# Decoder16_1.net
KiCad netlist of a schematic drawn in EAGLE
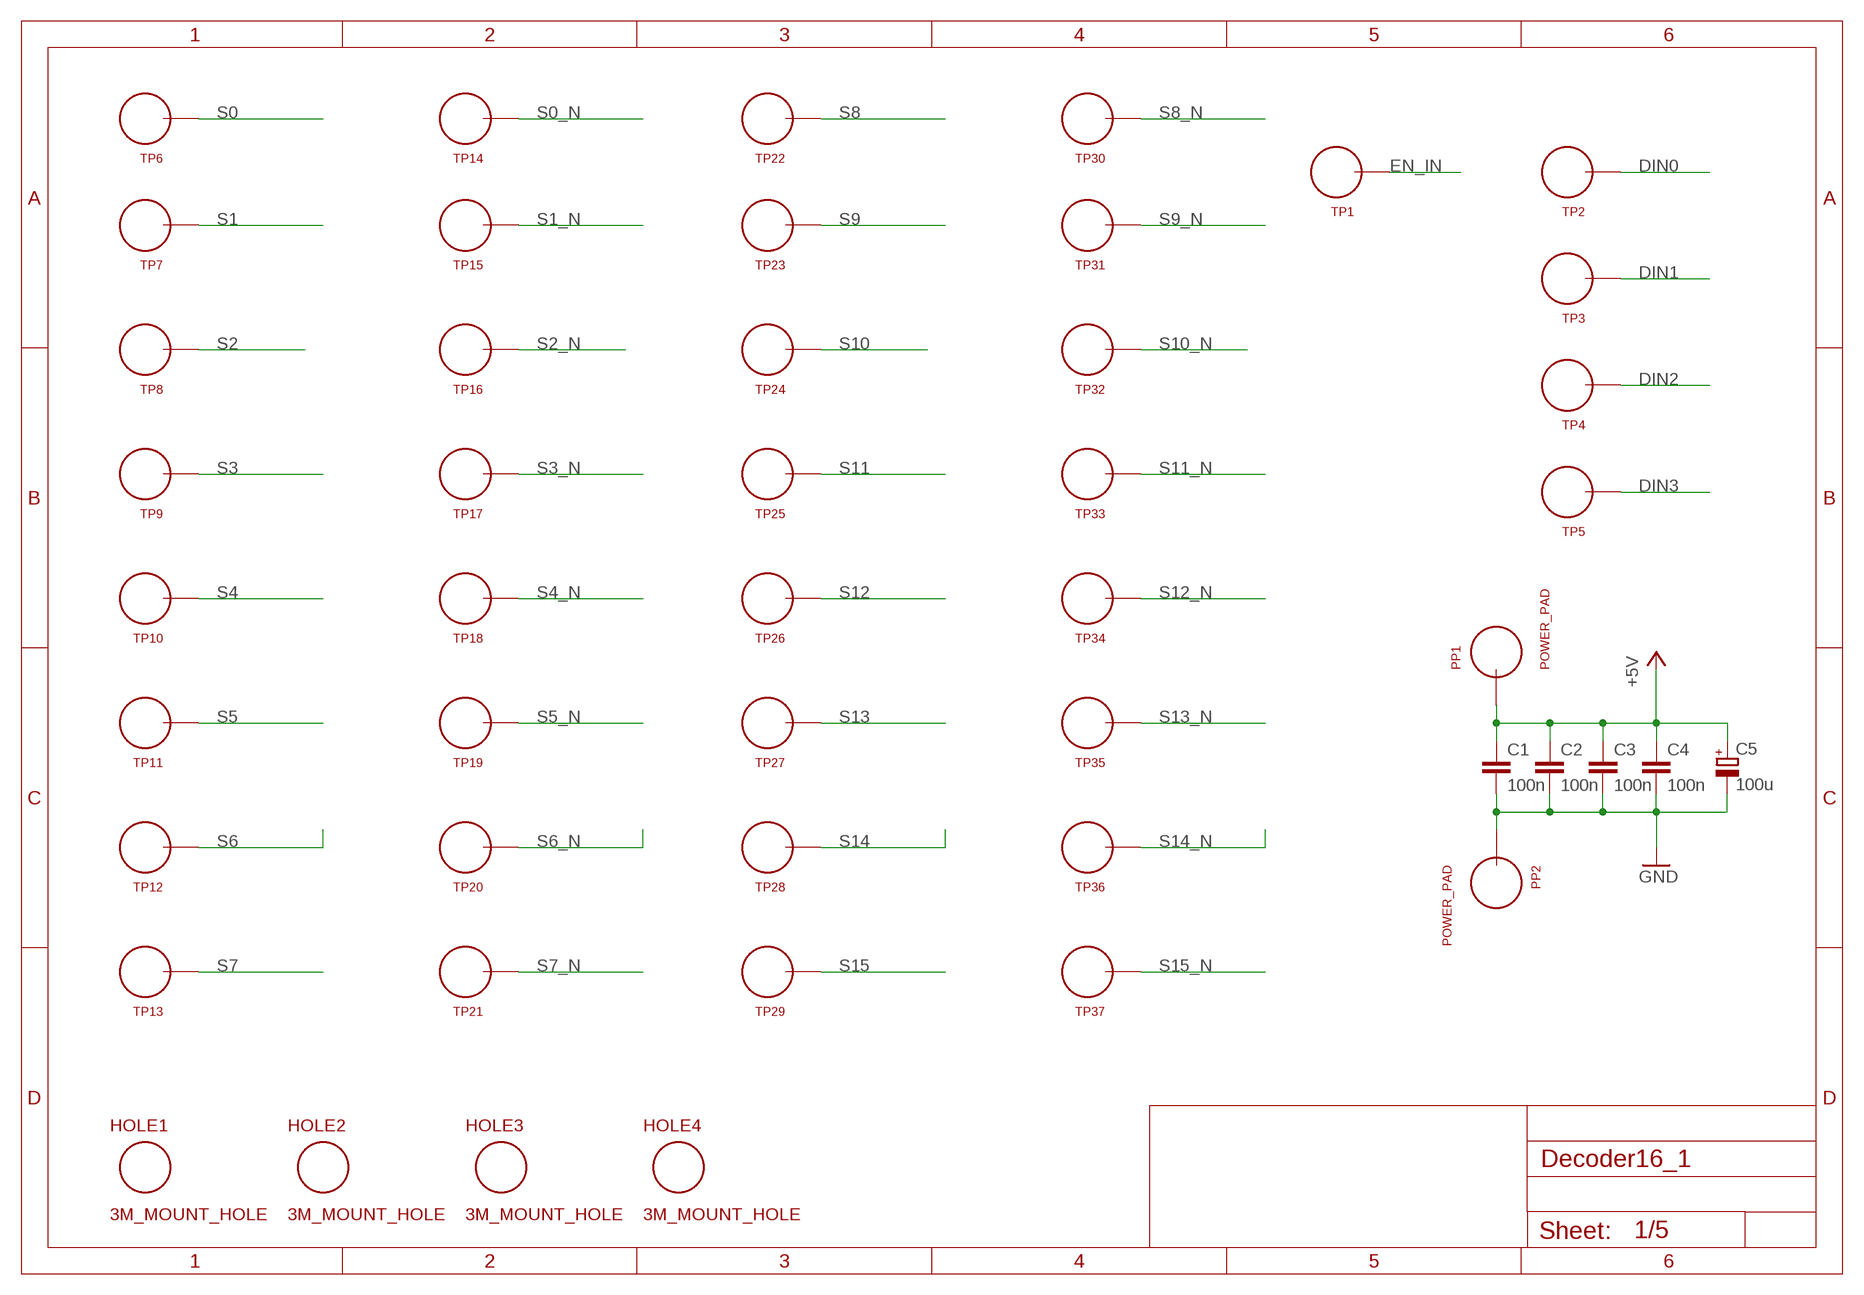
[diagram p0: schematic, sheet 1]
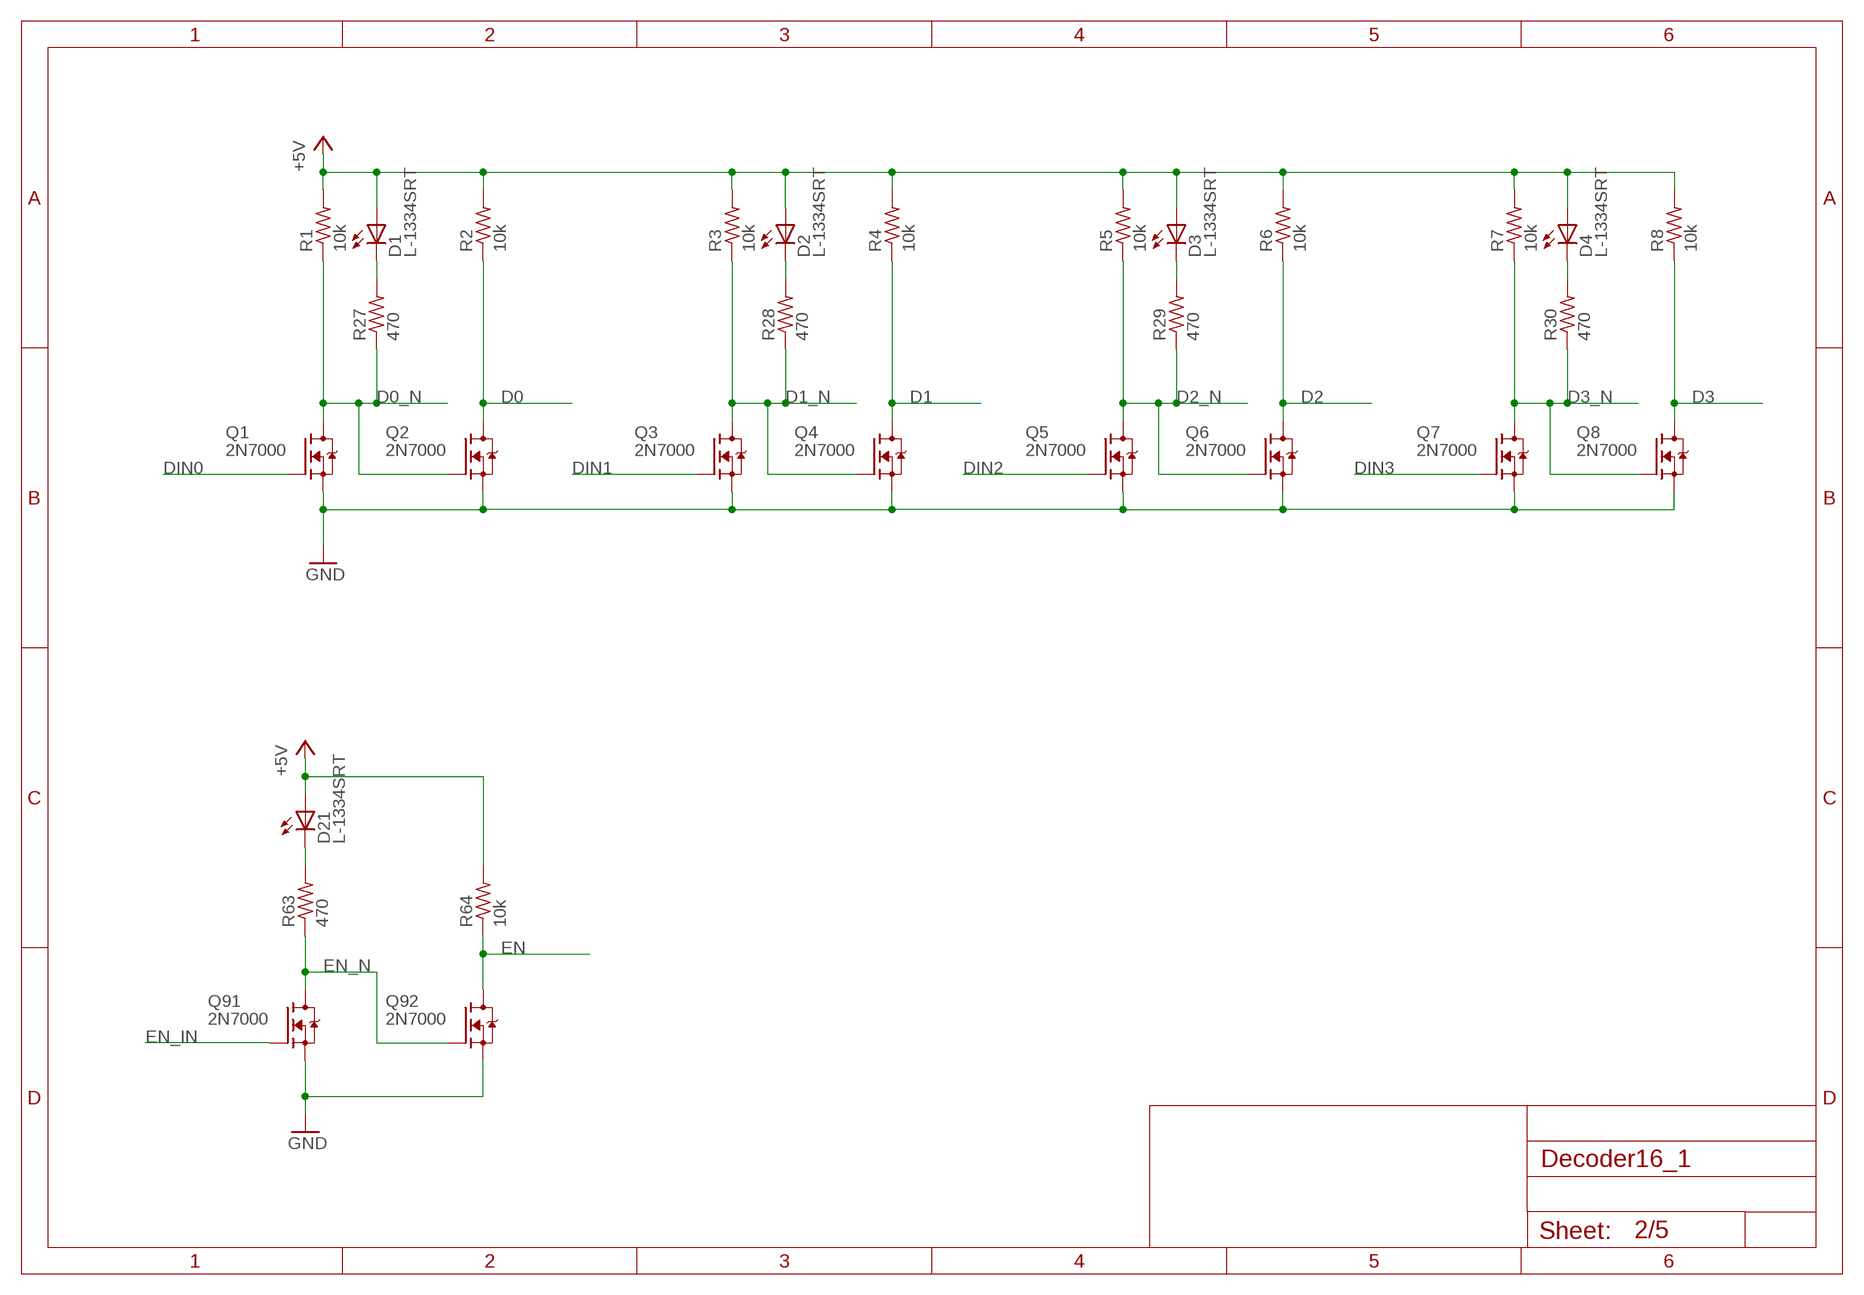
[diagram p1: schematic, sheet 2]
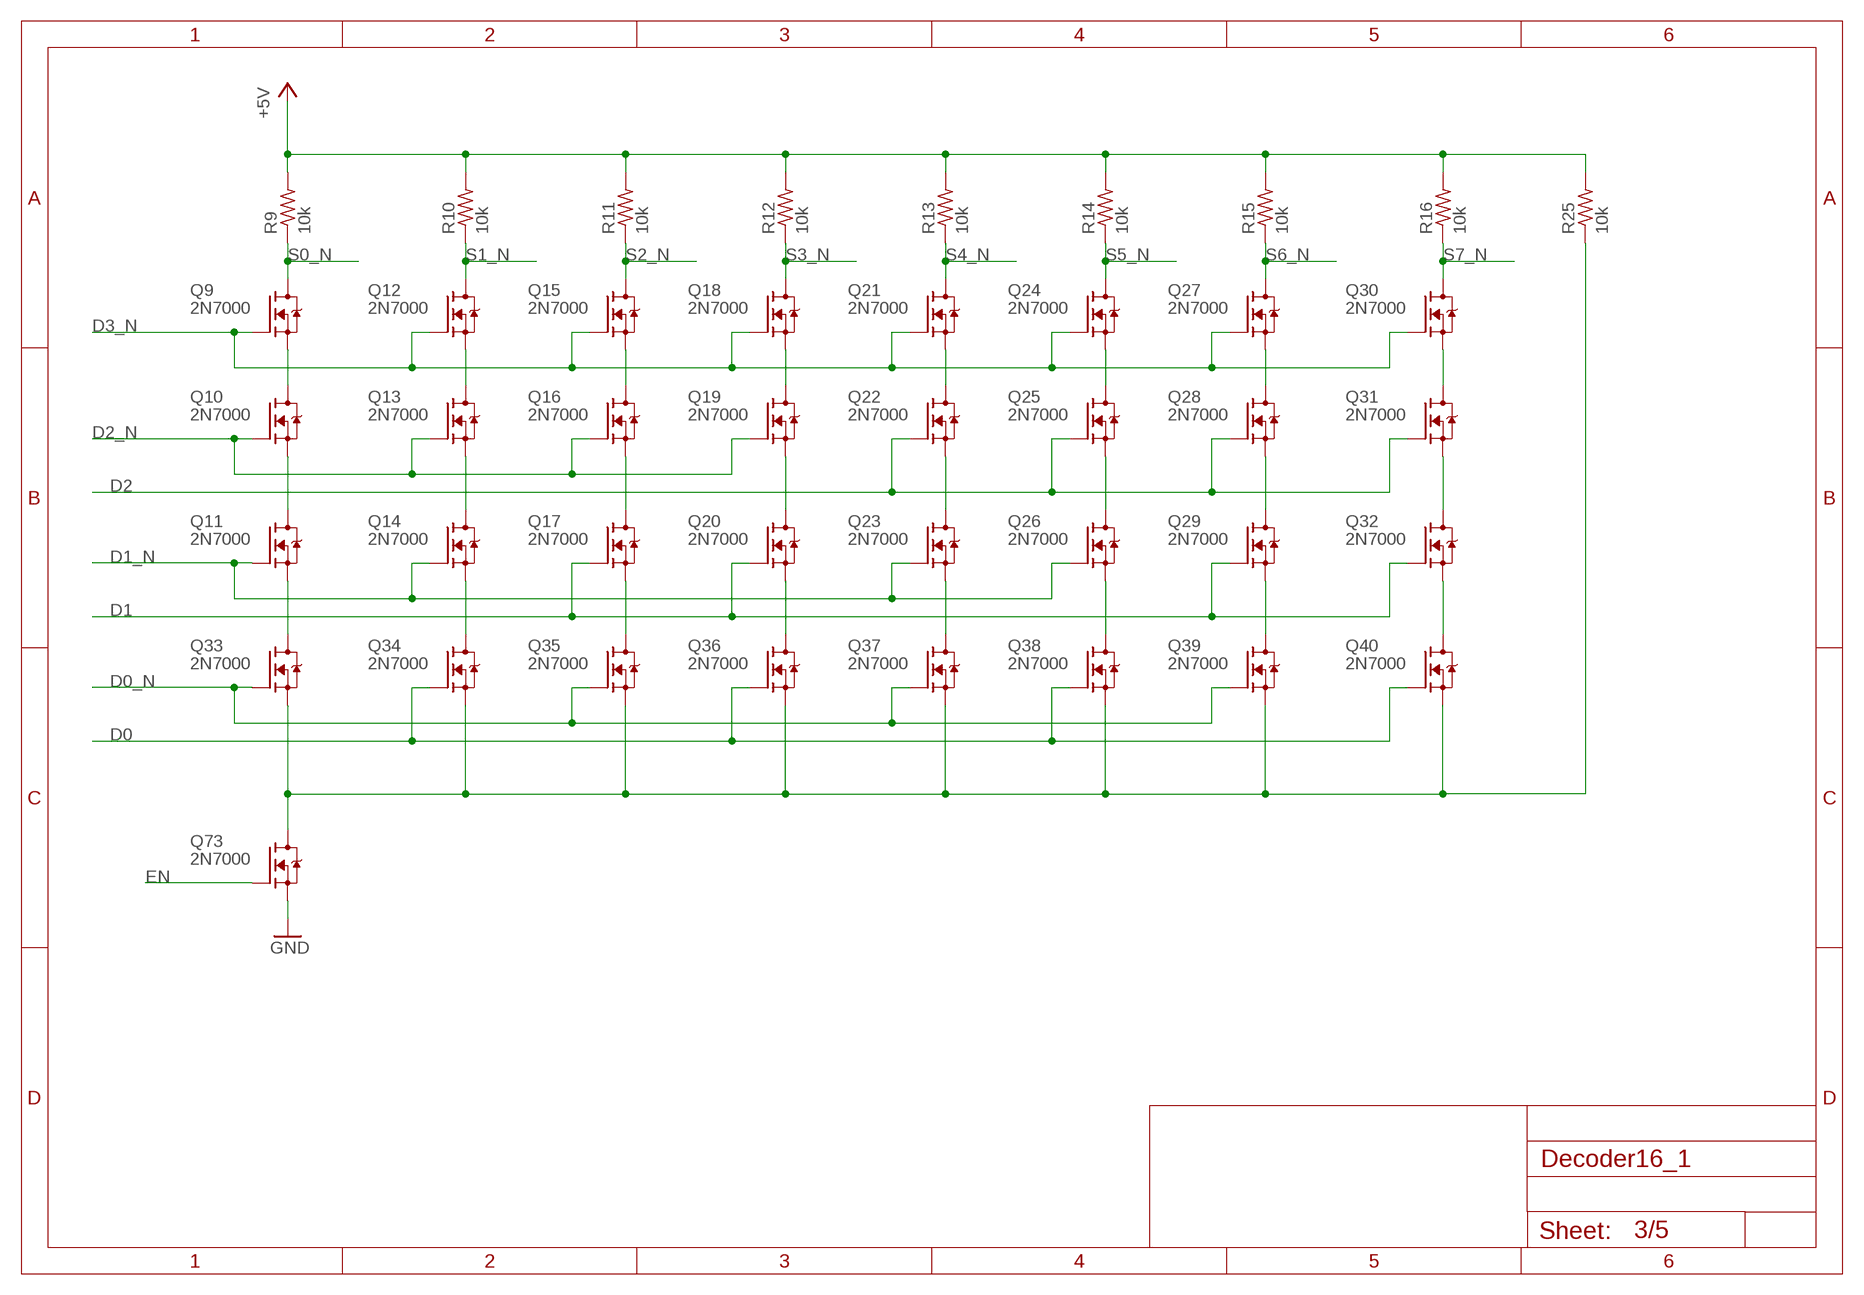
[diagram p2: schematic, sheet 3]
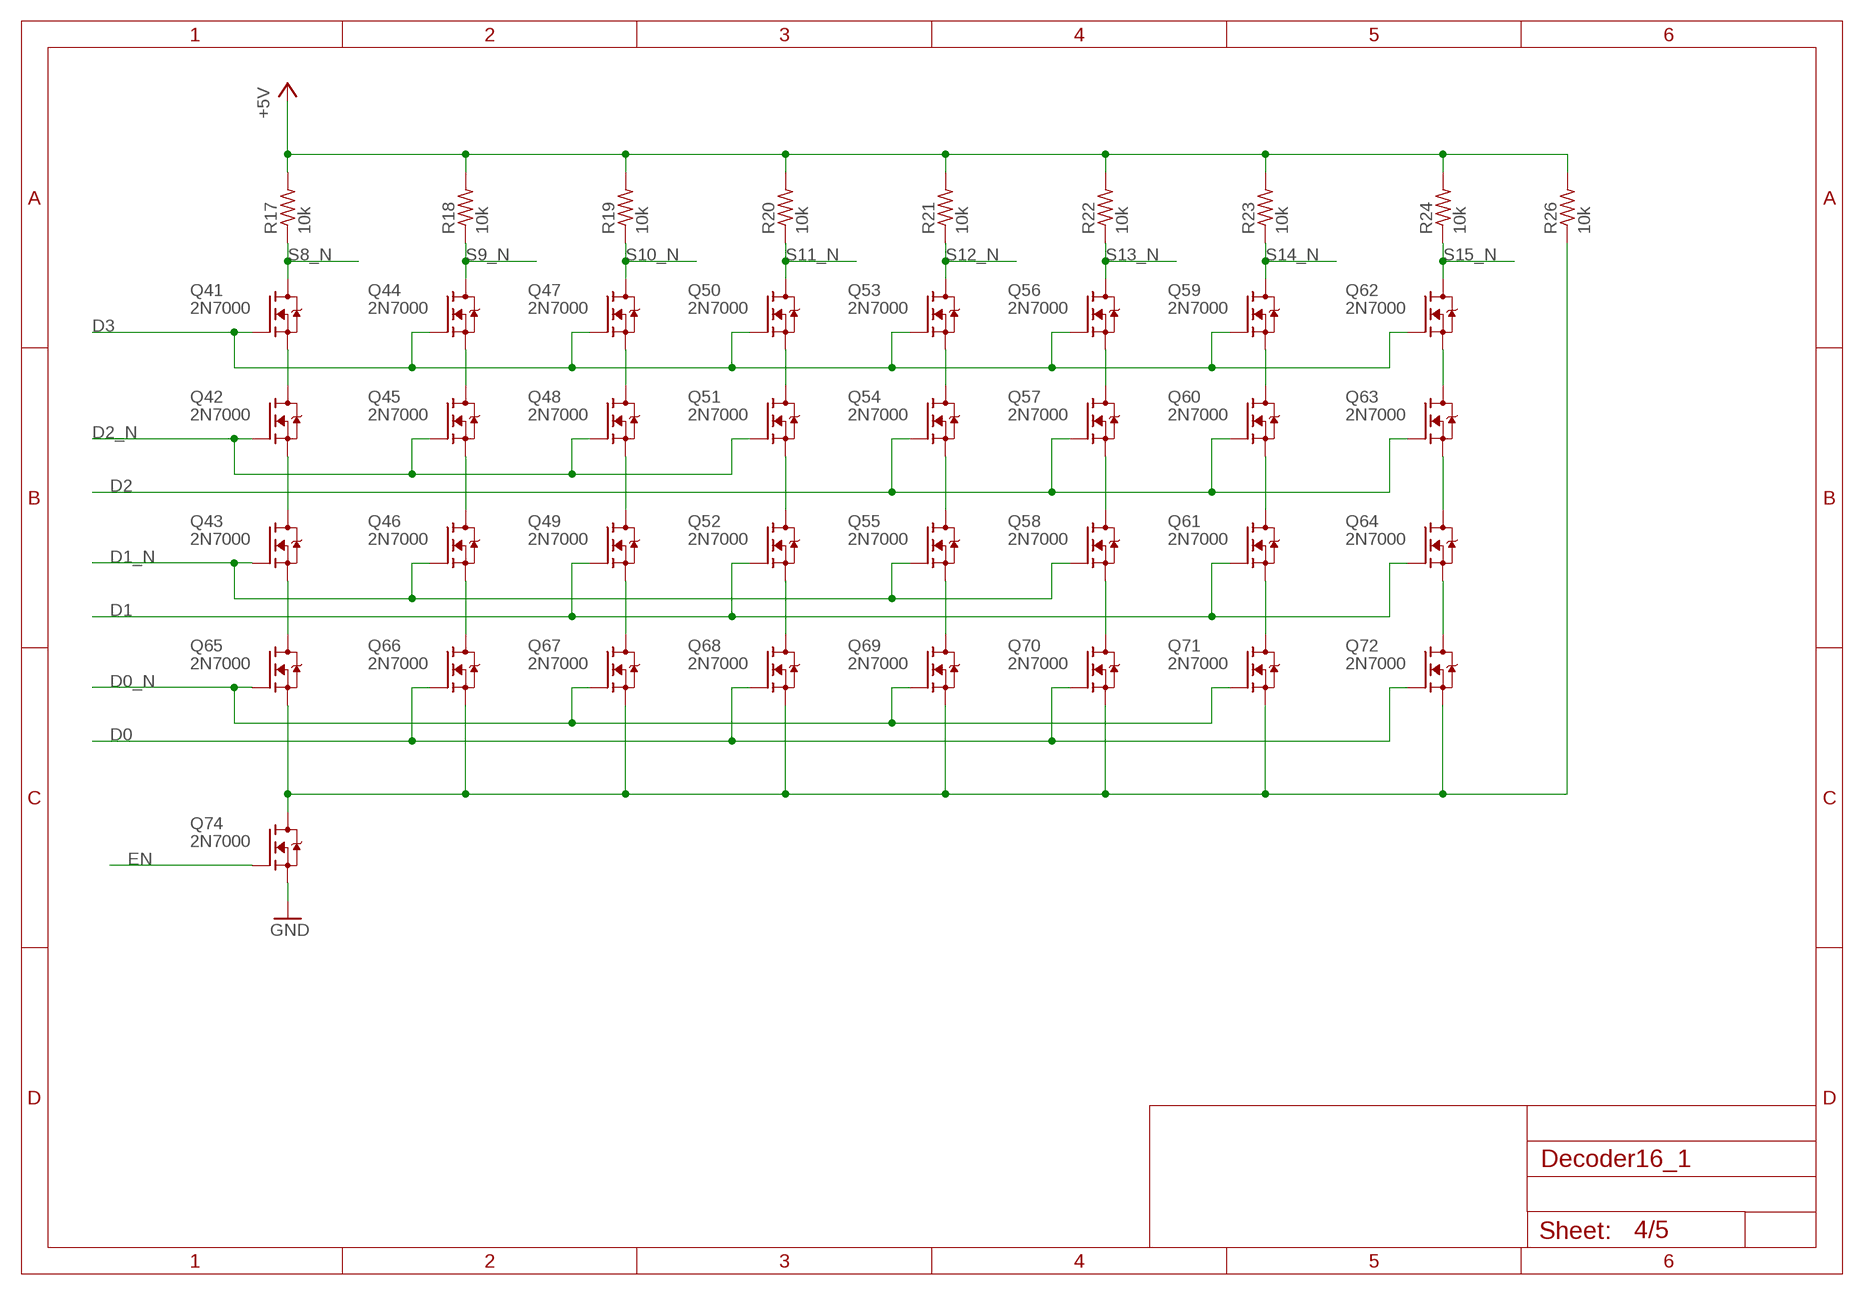
[diagram p3: schematic, sheet 4]
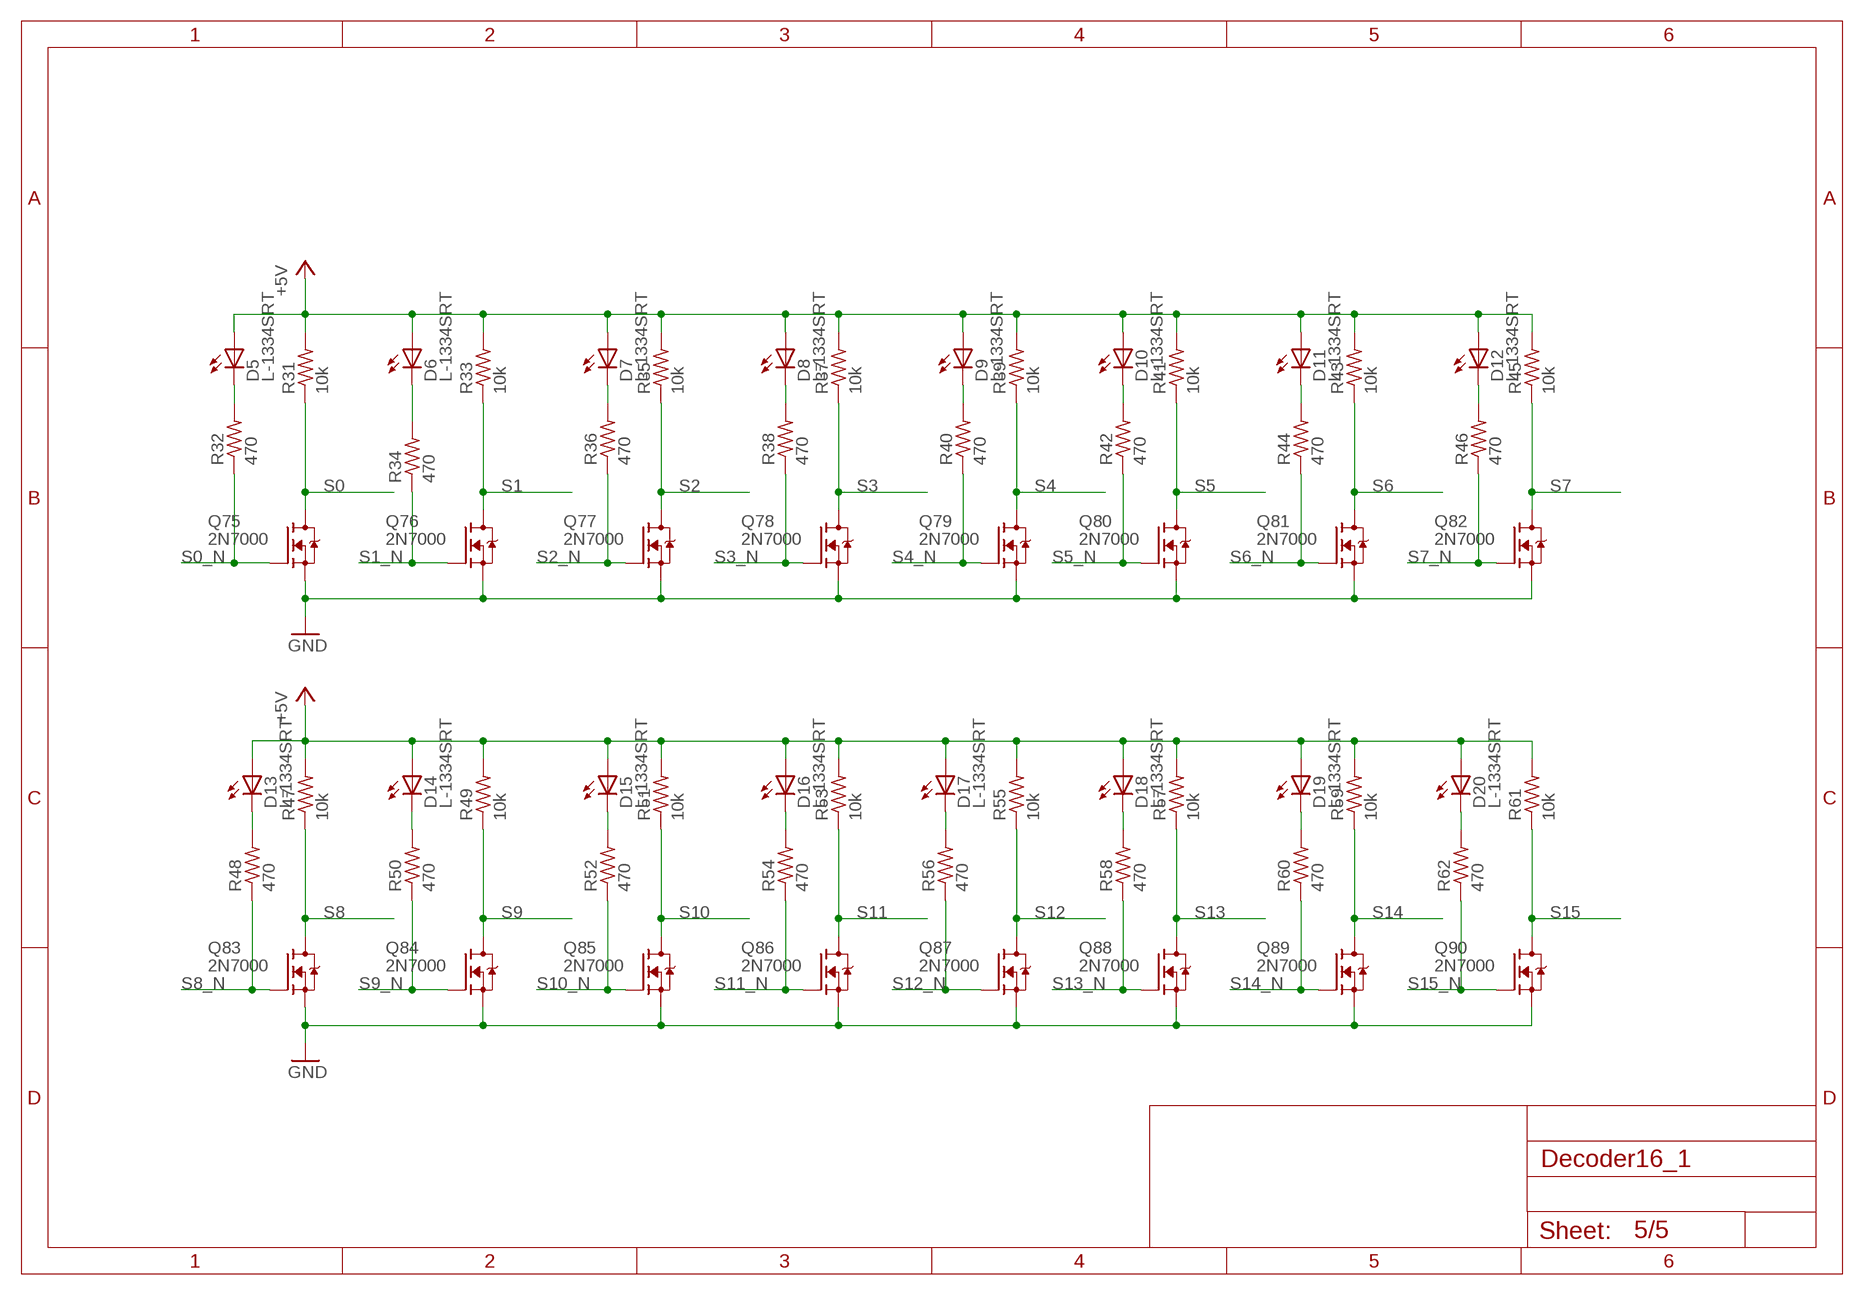
[diagram p4: schematic, sheet 5]

(export (version "E")
  (design (tool "Eeschema 10.0.6"))
  (components
    (comp (ref "C1")
      (value "100n")
      (footprint "eagle-import:CAP_P2INCH")
      (libsource (lib "eagle-import") (part "C_P2INCH"))
    )
    (comp (ref "C2")
      (value "100n")
      (footprint "eagle-import:CAP_P2INCH")
      (libsource (lib "eagle-import") (part "C_P2INCH"))
    )
    (comp (ref "C3")
      (value "100n")
      (footprint "eagle-import:CAP_P2INCH")
      (libsource (lib "eagle-import") (part "C_P2INCH"))
    )
    (comp (ref "C4")
      (value "100n")
      (footprint "eagle-import:CAP_P2INCH")
      (libsource (lib "eagle-import") (part "C_P2INCH"))
    )
    (comp (ref "C5")
      (value "100u")
      (footprint "eagle-import:POLARISED_CAP_2P5_6P3MM")
      (libsource (lib "eagle-import") (part "POLARISED_CAP_2P5_6P3MM"))
    )
    (comp (ref "HOLE1")
      (value "3M_MOUNT_HOLE")
      (footprint "eagle-import:3M_HOLE")
      (libsource (lib "eagle-import") (part "3M_MOUNT_HOLE"))
    )
    (comp (ref "HOLE2")
      (value "3M_MOUNT_HOLE")
      (footprint "eagle-import:3M_HOLE")
      (libsource (lib "eagle-import") (part "3M_MOUNT_HOLE"))
    )
    (comp (ref "HOLE3")
      (value "3M_MOUNT_HOLE")
      (footprint "eagle-import:3M_HOLE")
      (libsource (lib "eagle-import") (part "3M_MOUNT_HOLE"))
    )
    (comp (ref "HOLE4")
      (value "3M_MOUNT_HOLE")
      (footprint "eagle-import:3M_HOLE")
      (libsource (lib "eagle-import") (part "3M_MOUNT_HOLE"))
    )
    (comp (ref "PP1")
      (value "POWER_PAD")
      (footprint "eagle-import:POWER_PAD")
      (libsource (lib "eagle-import") (part "POWER_PAD"))
    )
    (comp (ref "PP2")
      (value "POWER_PAD")
      (footprint "eagle-import:POWER_PAD")
      (libsource (lib "eagle-import") (part "POWER_PAD"))
    )
    (comp (ref "TP1")
      (value "TEST_LOOP")
      (footprint "eagle-import:TEST_LOOP")
      (libsource (lib "eagle-import") (part "TEST_LOOP"))
    )
    (comp (ref "TP2")
      (value "TEST_LOOP")
      (footprint "eagle-import:TEST_LOOP")
      (libsource (lib "eagle-import") (part "TEST_LOOP"))
    )
    (comp (ref "TP3")
      (value "TEST_LOOP")
      (footprint "eagle-import:TEST_LOOP")
      (libsource (lib "eagle-import") (part "TEST_LOOP"))
    )
    (comp (ref "TP4")
      (value "TEST_LOOP")
      (footprint "eagle-import:TEST_LOOP")
      (libsource (lib "eagle-import") (part "TEST_LOOP"))
    )
    (comp (ref "TP5")
      (value "TEST_LOOP")
      (footprint "eagle-import:TEST_LOOP")
      (libsource (lib "eagle-import") (part "TEST_LOOP"))
    )
    (comp (ref "TP6")
      (value "TEST_LOOP")
      (footprint "eagle-import:TEST_LOOP")
      (libsource (lib "eagle-import") (part "TEST_LOOP"))
    )
    (comp (ref "TP7")
      (value "TEST_LOOP")
      (footprint "eagle-import:TEST_LOOP")
      (libsource (lib "eagle-import") (part "TEST_LOOP"))
    )
    (comp (ref "TP8")
      (value "TEST_LOOP")
      (footprint "eagle-import:TEST_LOOP")
      (libsource (lib "eagle-import") (part "TEST_LOOP"))
    )
    (comp (ref "TP9")
      (value "TEST_LOOP")
      (footprint "eagle-import:TEST_LOOP")
      (libsource (lib "eagle-import") (part "TEST_LOOP"))
    )
    (comp (ref "TP10")
      (value "TEST_LOOP")
      (footprint "eagle-import:TEST_LOOP")
      (libsource (lib "eagle-import") (part "TEST_LOOP"))
    )
    (comp (ref "TP11")
      (value "TEST_LOOP")
      (footprint "eagle-import:TEST_LOOP")
      (libsource (lib "eagle-import") (part "TEST_LOOP"))
    )
    (comp (ref "TP12")
      (value "TEST_LOOP")
      (footprint "eagle-import:TEST_LOOP")
      (libsource (lib "eagle-import") (part "TEST_LOOP"))
    )
    (comp (ref "TP13")
      (value "TEST_LOOP")
      (footprint "eagle-import:TEST_LOOP")
      (libsource (lib "eagle-import") (part "TEST_LOOP"))
    )
    (comp (ref "TP14")
      (value "TEST_LOOP")
      (footprint "eagle-import:TEST_LOOP")
      (libsource (lib "eagle-import") (part "TEST_LOOP"))
    )
    (comp (ref "TP15")
      (value "TEST_LOOP")
      (footprint "eagle-import:TEST_LOOP")
      (libsource (lib "eagle-import") (part "TEST_LOOP"))
    )
    (comp (ref "TP16")
      (value "TEST_LOOP")
      (footprint "eagle-import:TEST_LOOP")
      (libsource (lib "eagle-import") (part "TEST_LOOP"))
    )
    (comp (ref "TP17")
      (value "TEST_LOOP")
      (footprint "eagle-import:TEST_LOOP")
      (libsource (lib "eagle-import") (part "TEST_LOOP"))
    )
    (comp (ref "TP18")
      (value "TEST_LOOP")
      (footprint "eagle-import:TEST_LOOP")
      (libsource (lib "eagle-import") (part "TEST_LOOP"))
    )
    (comp (ref "TP19")
      (value "TEST_LOOP")
      (footprint "eagle-import:TEST_LOOP")
      (libsource (lib "eagle-import") (part "TEST_LOOP"))
    )
    (comp (ref "TP20")
      (value "TEST_LOOP")
      (footprint "eagle-import:TEST_LOOP")
      (libsource (lib "eagle-import") (part "TEST_LOOP"))
    )
    (comp (ref "TP21")
      (value "TEST_LOOP")
      (footprint "eagle-import:TEST_LOOP")
      (libsource (lib "eagle-import") (part "TEST_LOOP"))
    )
    (comp (ref "TP22")
      (value "TEST_LOOP")
      (footprint "eagle-import:TEST_LOOP")
      (libsource (lib "eagle-import") (part "TEST_LOOP"))
    )
    (comp (ref "TP23")
      (value "TEST_LOOP")
      (footprint "eagle-import:TEST_LOOP")
      (libsource (lib "eagle-import") (part "TEST_LOOP"))
    )
    (comp (ref "TP24")
      (value "TEST_LOOP")
      (footprint "eagle-import:TEST_LOOP")
      (libsource (lib "eagle-import") (part "TEST_LOOP"))
    )
    (comp (ref "TP25")
      (value "TEST_LOOP")
      (footprint "eagle-import:TEST_LOOP")
      (libsource (lib "eagle-import") (part "TEST_LOOP"))
    )
    (comp (ref "TP26")
      (value "TEST_LOOP")
      (footprint "eagle-import:TEST_LOOP")
      (libsource (lib "eagle-import") (part "TEST_LOOP"))
    )
    (comp (ref "TP27")
      (value "TEST_LOOP")
      (footprint "eagle-import:TEST_LOOP")
      (libsource (lib "eagle-import") (part "TEST_LOOP"))
    )
    (comp (ref "TP28")
      (value "TEST_LOOP")
      (footprint "eagle-import:TEST_LOOP")
      (libsource (lib "eagle-import") (part "TEST_LOOP"))
    )
    (comp (ref "TP29")
      (value "TEST_LOOP")
      (footprint "eagle-import:TEST_LOOP")
      (libsource (lib "eagle-import") (part "TEST_LOOP"))
    )
    (comp (ref "TP30")
      (value "TEST_LOOP")
      (footprint "eagle-import:TEST_LOOP")
      (libsource (lib "eagle-import") (part "TEST_LOOP"))
    )
    (comp (ref "TP31")
      (value "TEST_LOOP")
      (footprint "eagle-import:TEST_LOOP")
      (libsource (lib "eagle-import") (part "TEST_LOOP"))
    )
    (comp (ref "TP32")
      (value "TEST_LOOP")
      (footprint "eagle-import:TEST_LOOP")
      (libsource (lib "eagle-import") (part "TEST_LOOP"))
    )
    (comp (ref "TP33")
      (value "TEST_LOOP")
      (footprint "eagle-import:TEST_LOOP")
      (libsource (lib "eagle-import") (part "TEST_LOOP"))
    )
    (comp (ref "TP34")
      (value "TEST_LOOP")
      (footprint "eagle-import:TEST_LOOP")
      (libsource (lib "eagle-import") (part "TEST_LOOP"))
    )
    (comp (ref "TP35")
      (value "TEST_LOOP")
      (footprint "eagle-import:TEST_LOOP")
      (libsource (lib "eagle-import") (part "TEST_LOOP"))
    )
    (comp (ref "TP36")
      (value "TEST_LOOP")
      (footprint "eagle-import:TEST_LOOP")
      (libsource (lib "eagle-import") (part "TEST_LOOP"))
    )
    (comp (ref "TP37")
      (value "TEST_LOOP")
      (footprint "eagle-import:TEST_LOOP")
      (libsource (lib "eagle-import") (part "TEST_LOOP"))
    )
    (comp (ref "D5")
      (value "L-1334SRT")
      (footprint "eagle-import:LED3MM")
      (libsource (lib "eagle-import") (part "L-1334SRT"))
    )
    (comp (ref "D6")
      (value "L-1334SRT")
      (footprint "eagle-import:LED3MM")
      (libsource (lib "eagle-import") (part "L-1334SRT"))
    )
    (comp (ref "D7")
      (value "L-1334SRT")
      (footprint "eagle-import:LED3MM")
      (libsource (lib "eagle-import") (part "L-1334SRT"))
    )
    (comp (ref "D8")
      (value "L-1334SRT")
      (footprint "eagle-import:LED3MM")
      (libsource (lib "eagle-import") (part "L-1334SRT"))
    )
    (comp (ref "D9")
      (value "L-1334SRT")
      (footprint "eagle-import:LED3MM")
      (libsource (lib "eagle-import") (part "L-1334SRT"))
    )
    (comp (ref "D10")
      (value "L-1334SRT")
      (footprint "eagle-import:LED3MM")
      (libsource (lib "eagle-import") (part "L-1334SRT"))
    )
    (comp (ref "D11")
      (value "L-1334SRT")
      (footprint "eagle-import:LED3MM")
      (libsource (lib "eagle-import") (part "L-1334SRT"))
    )
    (comp (ref "D12")
      (value "L-1334SRT")
      (footprint "eagle-import:LED3MM")
      (libsource (lib "eagle-import") (part "L-1334SRT"))
    )
    (comp (ref "D13")
      (value "L-1334SRT")
      (footprint "eagle-import:LED3MM")
      (libsource (lib "eagle-import") (part "L-1334SRT"))
    )
    (comp (ref "D14")
      (value "L-1334SRT")
      (footprint "eagle-import:LED3MM")
      (libsource (lib "eagle-import") (part "L-1334SRT"))
    )
    (comp (ref "D15")
      (value "L-1334SRT")
      (footprint "eagle-import:LED3MM")
      (libsource (lib "eagle-import") (part "L-1334SRT"))
    )
    (comp (ref "D16")
      (value "L-1334SRT")
      (footprint "eagle-import:LED3MM")
      (libsource (lib "eagle-import") (part "L-1334SRT"))
    )
    (comp (ref "D17")
      (value "L-1334SRT")
      (footprint "eagle-import:LED3MM")
      (libsource (lib "eagle-import") (part "L-1334SRT"))
    )
    (comp (ref "D18")
      (value "L-1334SRT")
      (footprint "eagle-import:LED3MM")
      (libsource (lib "eagle-import") (part "L-1334SRT"))
    )
    (comp (ref "D19")
      (value "L-1334SRT")
      (footprint "eagle-import:LED3MM")
      (libsource (lib "eagle-import") (part "L-1334SRT"))
    )
    (comp (ref "D20")
      (value "L-1334SRT")
      (footprint "eagle-import:LED3MM")
      (libsource (lib "eagle-import") (part "L-1334SRT"))
    )
    (comp (ref "Q75")
      (value "2N7000")
      (footprint "eagle-import:TO92-DGS")
      (libsource (lib "eagle-import") (part "2N7000"))
    )
    (comp (ref "Q76")
      (value "2N7000")
      (footprint "eagle-import:TO92-DGS")
      (libsource (lib "eagle-import") (part "2N7000"))
    )
    (comp (ref "Q77")
      (value "2N7000")
      (footprint "eagle-import:TO92-DGS")
      (libsource (lib "eagle-import") (part "2N7000"))
    )
    (comp (ref "Q78")
      (value "2N7000")
      (footprint "eagle-import:TO92-DGS")
      (libsource (lib "eagle-import") (part "2N7000"))
    )
    (comp (ref "Q79")
      (value "2N7000")
      (footprint "eagle-import:TO92-DGS")
      (libsource (lib "eagle-import") (part "2N7000"))
    )
    (comp (ref "Q80")
      (value "2N7000")
      (footprint "eagle-import:TO92-DGS")
      (libsource (lib "eagle-import") (part "2N7000"))
    )
    (comp (ref "Q81")
      (value "2N7000")
      (footprint "eagle-import:TO92-DGS")
      (libsource (lib "eagle-import") (part "2N7000"))
    )
    (comp (ref "Q82")
      (value "2N7000")
      (footprint "eagle-import:TO92-DGS")
      (libsource (lib "eagle-import") (part "2N7000"))
    )
    (comp (ref "Q83")
      (value "2N7000")
      (footprint "eagle-import:TO92-DGS")
      (libsource (lib "eagle-import") (part "2N7000"))
    )
    (comp (ref "Q84")
      (value "2N7000")
      (footprint "eagle-import:TO92-DGS")
      (libsource (lib "eagle-import") (part "2N7000"))
    )
    (comp (ref "Q85")
      (value "2N7000")
      (footprint "eagle-import:TO92-DGS")
      (libsource (lib "eagle-import") (part "2N7000"))
    )
    (comp (ref "Q86")
      (value "2N7000")
      (footprint "eagle-import:TO92-DGS")
      (libsource (lib "eagle-import") (part "2N7000"))
    )
    (comp (ref "Q87")
      (value "2N7000")
      (footprint "eagle-import:TO92-DGS")
      (libsource (lib "eagle-import") (part "2N7000"))
    )
    (comp (ref "Q88")
      (value "2N7000")
      (footprint "eagle-import:TO92-DGS")
      (libsource (lib "eagle-import") (part "2N7000"))
    )
    (comp (ref "Q89")
      (value "2N7000")
      (footprint "eagle-import:TO92-DGS")
      (libsource (lib "eagle-import") (part "2N7000"))
    )
    (comp (ref "Q90")
      (value "2N7000")
      (footprint "eagle-import:TO92-DGS")
      (libsource (lib "eagle-import") (part "2N7000"))
    )
    (comp (ref "R31")
      (value "10k")
      (footprint "eagle-import:R_P2INCH")
      (libsource (lib "eagle-import") (part "R_P2INCH"))
    )
    (comp (ref "R32")
      (value "470")
      (footprint "eagle-import:R_P2INCH")
      (libsource (lib "eagle-import") (part "R_P2INCH"))
    )
    (comp (ref "R33")
      (value "10k")
      (footprint "eagle-import:R_P2INCH")
      (libsource (lib "eagle-import") (part "R_P2INCH"))
    )
    (comp (ref "R34")
      (value "470")
      (footprint "eagle-import:R_P2INCH")
      (libsource (lib "eagle-import") (part "R_P2INCH"))
    )
    (comp (ref "R35")
      (value "10k")
      (footprint "eagle-import:R_P2INCH")
      (libsource (lib "eagle-import") (part "R_P2INCH"))
    )
    (comp (ref "R36")
      (value "470")
      (footprint "eagle-import:R_P2INCH")
      (libsource (lib "eagle-import") (part "R_P2INCH"))
    )
    (comp (ref "R37")
      (value "10k")
      (footprint "eagle-import:R_P2INCH")
      (libsource (lib "eagle-import") (part "R_P2INCH"))
    )
    (comp (ref "R38")
      (value "470")
      (footprint "eagle-import:R_P2INCH")
      (libsource (lib "eagle-import") (part "R_P2INCH"))
    )
    (comp (ref "R39")
      (value "10k")
      (footprint "eagle-import:R_P2INCH")
      (libsource (lib "eagle-import") (part "R_P2INCH"))
    )
    (comp (ref "R40")
      (value "470")
      (footprint "eagle-import:R_P2INCH")
      (libsource (lib "eagle-import") (part "R_P2INCH"))
    )
    (comp (ref "R41")
      (value "10k")
      (footprint "eagle-import:R_P2INCH")
      (libsource (lib "eagle-import") (part "R_P2INCH"))
    )
    (comp (ref "R42")
      (value "470")
      (footprint "eagle-import:R_P2INCH")
      (libsource (lib "eagle-import") (part "R_P2INCH"))
    )
    (comp (ref "R43")
      (value "10k")
      (footprint "eagle-import:R_P2INCH")
      (libsource (lib "eagle-import") (part "R_P2INCH"))
    )
    (comp (ref "R44")
      (value "470")
      (footprint "eagle-import:R_P2INCH")
      (libsource (lib "eagle-import") (part "R_P2INCH"))
    )
    (comp (ref "R45")
      (value "10k")
      (footprint "eagle-import:R_P2INCH")
      (libsource (lib "eagle-import") (part "R_P2INCH"))
    )
    (comp (ref "R46")
      (value "470")
      (footprint "eagle-import:R_P2INCH")
      (libsource (lib "eagle-import") (part "R_P2INCH"))
    )
    (comp (ref "R47")
      (value "10k")
      (footprint "eagle-import:R_P2INCH")
      (libsource (lib "eagle-import") (part "R_P2INCH"))
    )
    (comp (ref "R48")
      (value "470")
      (footprint "eagle-import:R_P2INCH")
      (libsource (lib "eagle-import") (part "R_P2INCH"))
    )
    (comp (ref "R49")
      (value "10k")
      (footprint "eagle-import:R_P2INCH")
      (libsource (lib "eagle-import") (part "R_P2INCH"))
    )
    (comp (ref "R50")
      (value "470")
      (footprint "eagle-import:R_P2INCH")
      (libsource (lib "eagle-import") (part "R_P2INCH"))
    )
    (comp (ref "R51")
      (value "10k")
      (footprint "eagle-import:R_P2INCH")
      (libsource (lib "eagle-import") (part "R_P2INCH"))
    )
    (comp (ref "R52")
      (value "470")
      (footprint "eagle-import:R_P2INCH")
      (libsource (lib "eagle-import") (part "R_P2INCH"))
    )
    (comp (ref "R53")
      (value "10k")
      (footprint "eagle-import:R_P2INCH")
      (libsource (lib "eagle-import") (part "R_P2INCH"))
    )
    (comp (ref "R54")
      (value "470")
      (footprint "eagle-import:R_P2INCH")
      (libsource (lib "eagle-import") (part "R_P2INCH"))
    )
    (comp (ref "R55")
      (value "10k")
      (footprint "eagle-import:R_P2INCH")
      (libsource (lib "eagle-import") (part "R_P2INCH"))
    )
    (comp (ref "R56")
      (value "470")
      (footprint "eagle-import:R_P2INCH")
      (libsource (lib "eagle-import") (part "R_P2INCH"))
    )
    (comp (ref "R57")
      (value "10k")
      (footprint "eagle-import:R_P2INCH")
      (libsource (lib "eagle-import") (part "R_P2INCH"))
    )
    (comp (ref "R58")
      (value "470")
      (footprint "eagle-import:R_P2INCH")
      (libsource (lib "eagle-import") (part "R_P2INCH"))
    )
    (comp (ref "R59")
      (value "10k")
      (footprint "eagle-import:R_P2INCH")
      (libsource (lib "eagle-import") (part "R_P2INCH"))
    )
    (comp (ref "R60")
      (value "470")
      (footprint "eagle-import:R_P2INCH")
      (libsource (lib "eagle-import") (part "R_P2INCH"))
    )
    (comp (ref "R61")
      (value "10k")
      (footprint "eagle-import:R_P2INCH")
      (libsource (lib "eagle-import") (part "R_P2INCH"))
    )
    (comp (ref "R62")
      (value "470")
      (footprint "eagle-import:R_P2INCH")
      (libsource (lib "eagle-import") (part "R_P2INCH"))
    )
    (comp (ref "Q9")
      (value "2N7000")
      (footprint "eagle-import:TO92-DGS")
      (libsource (lib "eagle-import") (part "2N7000"))
    )
    (comp (ref "Q10")
      (value "2N7000")
      (footprint "eagle-import:TO92-DGS")
      (libsource (lib "eagle-import") (part "2N7000"))
    )
    (comp (ref "Q11")
      (value "2N7000")
      (footprint "eagle-import:TO92-DGS")
      (libsource (lib "eagle-import") (part "2N7000"))
    )
    (comp (ref "Q12")
      (value "2N7000")
      (footprint "eagle-import:TO92-DGS")
      (libsource (lib "eagle-import") (part "2N7000"))
    )
    (comp (ref "Q13")
      (value "2N7000")
      (footprint "eagle-import:TO92-DGS")
      (libsource (lib "eagle-import") (part "2N7000"))
    )
    (comp (ref "Q14")
      (value "2N7000")
      (footprint "eagle-import:TO92-DGS")
      (libsource (lib "eagle-import") (part "2N7000"))
    )
    (comp (ref "Q15")
      (value "2N7000")
      (footprint "eagle-import:TO92-DGS")
      (libsource (lib "eagle-import") (part "2N7000"))
    )
    (comp (ref "Q16")
      (value "2N7000")
      (footprint "eagle-import:TO92-DGS")
      (libsource (lib "eagle-import") (part "2N7000"))
    )
    (comp (ref "Q17")
      (value "2N7000")
      (footprint "eagle-import:TO92-DGS")
      (libsource (lib "eagle-import") (part "2N7000"))
    )
    (comp (ref "Q18")
      (value "2N7000")
      (footprint "eagle-import:TO92-DGS")
      (libsource (lib "eagle-import") (part "2N7000"))
    )
    (comp (ref "Q19")
      (value "2N7000")
      (footprint "eagle-import:TO92-DGS")
      (libsource (lib "eagle-import") (part "2N7000"))
    )
    (comp (ref "Q20")
      (value "2N7000")
      (footprint "eagle-import:TO92-DGS")
      (libsource (lib "eagle-import") (part "2N7000"))
    )
    (comp (ref "Q21")
      (value "2N7000")
      (footprint "eagle-import:TO92-DGS")
      (libsource (lib "eagle-import") (part "2N7000"))
    )
    (comp (ref "Q22")
      (value "2N7000")
      (footprint "eagle-import:TO92-DGS")
      (libsource (lib "eagle-import") (part "2N7000"))
    )
    (comp (ref "Q23")
      (value "2N7000")
      (footprint "eagle-import:TO92-DGS")
      (libsource (lib "eagle-import") (part "2N7000"))
    )
    (comp (ref "Q24")
      (value "2N7000")
      (footprint "eagle-import:TO92-DGS")
      (libsource (lib "eagle-import") (part "2N7000"))
    )
    (comp (ref "Q25")
      (value "2N7000")
      (footprint "eagle-import:TO92-DGS")
      (libsource (lib "eagle-import") (part "2N7000"))
    )
    (comp (ref "Q26")
      (value "2N7000")
      (footprint "eagle-import:TO92-DGS")
      (libsource (lib "eagle-import") (part "2N7000"))
    )
    (comp (ref "Q27")
      (value "2N7000")
      (footprint "eagle-import:TO92-DGS")
      (libsource (lib "eagle-import") (part "2N7000"))
    )
    (comp (ref "Q28")
      (value "2N7000")
      (footprint "eagle-import:TO92-DGS")
      (libsource (lib "eagle-import") (part "2N7000"))
    )
    (comp (ref "Q29")
      (value "2N7000")
      (footprint "eagle-import:TO92-DGS")
      (libsource (lib "eagle-import") (part "2N7000"))
    )
    (comp (ref "Q30")
      (value "2N7000")
      (footprint "eagle-import:TO92-DGS")
      (libsource (lib "eagle-import") (part "2N7000"))
    )
    (comp (ref "Q31")
      (value "2N7000")
      (footprint "eagle-import:TO92-DGS")
      (libsource (lib "eagle-import") (part "2N7000"))
    )
    (comp (ref "Q32")
      (value "2N7000")
      (footprint "eagle-import:TO92-DGS")
      (libsource (lib "eagle-import") (part "2N7000"))
    )
    (comp (ref "Q33")
      (value "2N7000")
      (footprint "eagle-import:TO92-DGS")
      (libsource (lib "eagle-import") (part "2N7000"))
    )
    (comp (ref "Q34")
      (value "2N7000")
      (footprint "eagle-import:TO92-DGS")
      (libsource (lib "eagle-import") (part "2N7000"))
    )
    (comp (ref "Q35")
      (value "2N7000")
      (footprint "eagle-import:TO92-DGS")
      (libsource (lib "eagle-import") (part "2N7000"))
    )
    (comp (ref "Q36")
      (value "2N7000")
      (footprint "eagle-import:TO92-DGS")
      (libsource (lib "eagle-import") (part "2N7000"))
    )
    (comp (ref "Q37")
      (value "2N7000")
      (footprint "eagle-import:TO92-DGS")
      (libsource (lib "eagle-import") (part "2N7000"))
    )
    (comp (ref "Q38")
      (value "2N7000")
      (footprint "eagle-import:TO92-DGS")
      (libsource (lib "eagle-import") (part "2N7000"))
    )
    (comp (ref "Q39")
      (value "2N7000")
      (footprint "eagle-import:TO92-DGS")
      (libsource (lib "eagle-import") (part "2N7000"))
    )
    (comp (ref "Q40")
      (value "2N7000")
      (footprint "eagle-import:TO92-DGS")
      (libsource (lib "eagle-import") (part "2N7000"))
    )
    (comp (ref "Q73")
      (value "2N7000")
      (footprint "eagle-import:TO92-DGS")
      (libsource (lib "eagle-import") (part "2N7000"))
    )
    (comp (ref "R9")
      (value "10k")
      (footprint "eagle-import:R_P2INCH")
      (libsource (lib "eagle-import") (part "R_P2INCH"))
    )
    (comp (ref "R10")
      (value "10k")
      (footprint "eagle-import:R_P2INCH")
      (libsource (lib "eagle-import") (part "R_P2INCH"))
    )
    (comp (ref "R11")
      (value "10k")
      (footprint "eagle-import:R_P2INCH")
      (libsource (lib "eagle-import") (part "R_P2INCH"))
    )
    (comp (ref "R12")
      (value "10k")
      (footprint "eagle-import:R_P2INCH")
      (libsource (lib "eagle-import") (part "R_P2INCH"))
    )
    (comp (ref "R13")
      (value "10k")
      (footprint "eagle-import:R_P2INCH")
      (libsource (lib "eagle-import") (part "R_P2INCH"))
    )
    (comp (ref "R14")
      (value "10k")
      (footprint "eagle-import:R_P2INCH")
      (libsource (lib "eagle-import") (part "R_P2INCH"))
    )
    (comp (ref "R15")
      (value "10k")
      (footprint "eagle-import:R_P2INCH")
      (libsource (lib "eagle-import") (part "R_P2INCH"))
    )
    (comp (ref "R16")
      (value "10k")
      (footprint "eagle-import:R_P2INCH")
      (libsource (lib "eagle-import") (part "R_P2INCH"))
    )
    (comp (ref "R25")
      (value "10k")
      (footprint "eagle-import:R_P2INCH")
      (libsource (lib "eagle-import") (part "R_P2INCH"))
    )
    (comp (ref "D1")
      (value "L-1334SRT")
      (footprint "eagle-import:LED3MM")
      (libsource (lib "eagle-import") (part "L-1334SRT"))
    )
    (comp (ref "D2")
      (value "L-1334SRT")
      (footprint "eagle-import:LED3MM")
      (libsource (lib "eagle-import") (part "L-1334SRT"))
    )
    (comp (ref "D3")
      (value "L-1334SRT")
      (footprint "eagle-import:LED3MM")
      (libsource (lib "eagle-import") (part "L-1334SRT"))
    )
    (comp (ref "D4")
      (value "L-1334SRT")
      (footprint "eagle-import:LED3MM")
      (libsource (lib "eagle-import") (part "L-1334SRT"))
    )
    (comp (ref "D21")
      (value "L-1334SRT")
      (footprint "eagle-import:LED3MM")
      (libsource (lib "eagle-import") (part "L-1334SRT"))
    )
    (comp (ref "Q1")
      (value "2N7000")
      (footprint "eagle-import:TO92-DGS")
      (libsource (lib "eagle-import") (part "2N7000"))
    )
    (comp (ref "Q2")
      (value "2N7000")
      (footprint "eagle-import:TO92-DGS")
      (libsource (lib "eagle-import") (part "2N7000"))
    )
    (comp (ref "Q3")
      (value "2N7000")
      (footprint "eagle-import:TO92-DGS")
      (libsource (lib "eagle-import") (part "2N7000"))
    )
    (comp (ref "Q4")
      (value "2N7000")
      (footprint "eagle-import:TO92-DGS")
      (libsource (lib "eagle-import") (part "2N7000"))
    )
    (comp (ref "Q5")
      (value "2N7000")
      (footprint "eagle-import:TO92-DGS")
      (libsource (lib "eagle-import") (part "2N7000"))
    )
    (comp (ref "Q6")
      (value "2N7000")
      (footprint "eagle-import:TO92-DGS")
      (libsource (lib "eagle-import") (part "2N7000"))
    )
    (comp (ref "Q7")
      (value "2N7000")
      (footprint "eagle-import:TO92-DGS")
      (libsource (lib "eagle-import") (part "2N7000"))
    )
    (comp (ref "Q8")
      (value "2N7000")
      (footprint "eagle-import:TO92-DGS")
      (libsource (lib "eagle-import") (part "2N7000"))
    )
    (comp (ref "Q91")
      (value "2N7000")
      (footprint "eagle-import:TO92-DGS")
      (libsource (lib "eagle-import") (part "2N7000"))
    )
    (comp (ref "Q92")
      (value "2N7000")
      (footprint "eagle-import:TO92-DGS")
      (libsource (lib "eagle-import") (part "2N7000"))
    )
    (comp (ref "R1")
      (value "10k")
      (footprint "eagle-import:R_P2INCH")
      (libsource (lib "eagle-import") (part "R_P2INCH"))
    )
    (comp (ref "R2")
      (value "10k")
      (footprint "eagle-import:R_P2INCH")
      (libsource (lib "eagle-import") (part "R_P2INCH"))
    )
    (comp (ref "R3")
      (value "10k")
      (footprint "eagle-import:R_P2INCH")
      (libsource (lib "eagle-import") (part "R_P2INCH"))
    )
    (comp (ref "R4")
      (value "10k")
      (footprint "eagle-import:R_P2INCH")
      (libsource (lib "eagle-import") (part "R_P2INCH"))
    )
    (comp (ref "R5")
      (value "10k")
      (footprint "eagle-import:R_P2INCH")
      (libsource (lib "eagle-import") (part "R_P2INCH"))
    )
    (comp (ref "R6")
      (value "10k")
      (footprint "eagle-import:R_P2INCH")
      (libsource (lib "eagle-import") (part "R_P2INCH"))
    )
    (comp (ref "R7")
      (value "10k")
      (footprint "eagle-import:R_P2INCH")
      (libsource (lib "eagle-import") (part "R_P2INCH"))
    )
    (comp (ref "R8")
      (value "10k")
      (footprint "eagle-import:R_P2INCH")
      (libsource (lib "eagle-import") (part "R_P2INCH"))
    )
    (comp (ref "R27")
      (value "470")
      (footprint "eagle-import:R_P2INCH")
      (libsource (lib "eagle-import") (part "R_P2INCH"))
    )
    (comp (ref "R28")
      (value "470")
      (footprint "eagle-import:R_P2INCH")
      (libsource (lib "eagle-import") (part "R_P2INCH"))
    )
    (comp (ref "R29")
      (value "470")
      (footprint "eagle-import:R_P2INCH")
      (libsource (lib "eagle-import") (part "R_P2INCH"))
    )
    (comp (ref "R30")
      (value "470")
      (footprint "eagle-import:R_P2INCH")
      (libsource (lib "eagle-import") (part "R_P2INCH"))
    )
    (comp (ref "R63")
      (value "470")
      (footprint "eagle-import:R_P2INCH")
      (libsource (lib "eagle-import") (part "R_P2INCH"))
    )
    (comp (ref "R64")
      (value "10k")
      (footprint "eagle-import:R_P2INCH")
      (libsource (lib "eagle-import") (part "R_P2INCH"))
    )
    (comp (ref "Q41")
      (value "2N7000")
      (footprint "eagle-import:TO92-DGS")
      (libsource (lib "eagle-import") (part "2N7000"))
    )
    (comp (ref "Q42")
      (value "2N7000")
      (footprint "eagle-import:TO92-DGS")
      (libsource (lib "eagle-import") (part "2N7000"))
    )
    (comp (ref "Q43")
      (value "2N7000")
      (footprint "eagle-import:TO92-DGS")
      (libsource (lib "eagle-import") (part "2N7000"))
    )
    (comp (ref "Q44")
      (value "2N7000")
      (footprint "eagle-import:TO92-DGS")
      (libsource (lib "eagle-import") (part "2N7000"))
    )
    (comp (ref "Q45")
      (value "2N7000")
      (footprint "eagle-import:TO92-DGS")
      (libsource (lib "eagle-import") (part "2N7000"))
    )
    (comp (ref "Q46")
      (value "2N7000")
      (footprint "eagle-import:TO92-DGS")
      (libsource (lib "eagle-import") (part "2N7000"))
    )
    (comp (ref "Q47")
      (value "2N7000")
      (footprint "eagle-import:TO92-DGS")
      (libsource (lib "eagle-import") (part "2N7000"))
    )
    (comp (ref "Q48")
      (value "2N7000")
      (footprint "eagle-import:TO92-DGS")
      (libsource (lib "eagle-import") (part "2N7000"))
    )
    (comp (ref "Q49")
      (value "2N7000")
      (footprint "eagle-import:TO92-DGS")
      (libsource (lib "eagle-import") (part "2N7000"))
    )
    (comp (ref "Q50")
      (value "2N7000")
      (footprint "eagle-import:TO92-DGS")
      (libsource (lib "eagle-import") (part "2N7000"))
    )
    (comp (ref "Q51")
      (value "2N7000")
      (footprint "eagle-import:TO92-DGS")
      (libsource (lib "eagle-import") (part "2N7000"))
    )
    (comp (ref "Q52")
      (value "2N7000")
      (footprint "eagle-import:TO92-DGS")
      (libsource (lib "eagle-import") (part "2N7000"))
    )
    (comp (ref "Q53")
      (value "2N7000")
      (footprint "eagle-import:TO92-DGS")
      (libsource (lib "eagle-import") (part "2N7000"))
    )
    (comp (ref "Q54")
      (value "2N7000")
      (footprint "eagle-import:TO92-DGS")
      (libsource (lib "eagle-import") (part "2N7000"))
    )
    (comp (ref "Q55")
      (value "2N7000")
      (footprint "eagle-import:TO92-DGS")
      (libsource (lib "eagle-import") (part "2N7000"))
    )
    (comp (ref "Q56")
      (value "2N7000")
      (footprint "eagle-import:TO92-DGS")
      (libsource (lib "eagle-import") (part "2N7000"))
    )
    (comp (ref "Q57")
      (value "2N7000")
      (footprint "eagle-import:TO92-DGS")
      (libsource (lib "eagle-import") (part "2N7000"))
    )
    (comp (ref "Q58")
      (value "2N7000")
      (footprint "eagle-import:TO92-DGS")
      (libsource (lib "eagle-import") (part "2N7000"))
    )
    (comp (ref "Q59")
      (value "2N7000")
      (footprint "eagle-import:TO92-DGS")
      (libsource (lib "eagle-import") (part "2N7000"))
    )
    (comp (ref "Q60")
      (value "2N7000")
      (footprint "eagle-import:TO92-DGS")
      (libsource (lib "eagle-import") (part "2N7000"))
    )
    (comp (ref "Q61")
      (value "2N7000")
      (footprint "eagle-import:TO92-DGS")
      (libsource (lib "eagle-import") (part "2N7000"))
    )
    (comp (ref "Q62")
      (value "2N7000")
      (footprint "eagle-import:TO92-DGS")
      (libsource (lib "eagle-import") (part "2N7000"))
    )
    (comp (ref "Q63")
      (value "2N7000")
      (footprint "eagle-import:TO92-DGS")
      (libsource (lib "eagle-import") (part "2N7000"))
    )
    (comp (ref "Q64")
      (value "2N7000")
      (footprint "eagle-import:TO92-DGS")
      (libsource (lib "eagle-import") (part "2N7000"))
    )
    (comp (ref "Q65")
      (value "2N7000")
      (footprint "eagle-import:TO92-DGS")
      (libsource (lib "eagle-import") (part "2N7000"))
    )
    (comp (ref "Q66")
      (value "2N7000")
      (footprint "eagle-import:TO92-DGS")
      (libsource (lib "eagle-import") (part "2N7000"))
    )
    (comp (ref "Q67")
      (value "2N7000")
      (footprint "eagle-import:TO92-DGS")
      (libsource (lib "eagle-import") (part "2N7000"))
    )
    (comp (ref "Q68")
      (value "2N7000")
      (footprint "eagle-import:TO92-DGS")
      (libsource (lib "eagle-import") (part "2N7000"))
    )
    (comp (ref "Q69")
      (value "2N7000")
      (footprint "eagle-import:TO92-DGS")
      (libsource (lib "eagle-import") (part "2N7000"))
    )
    (comp (ref "Q70")
      (value "2N7000")
      (footprint "eagle-import:TO92-DGS")
      (libsource (lib "eagle-import") (part "2N7000"))
    )
    (comp (ref "Q71")
      (value "2N7000")
      (footprint "eagle-import:TO92-DGS")
      (libsource (lib "eagle-import") (part "2N7000"))
    )
    (comp (ref "Q72")
      (value "2N7000")
      (footprint "eagle-import:TO92-DGS")
      (libsource (lib "eagle-import") (part "2N7000"))
    )
    (comp (ref "Q74")
      (value "2N7000")
      (footprint "eagle-import:TO92-DGS")
      (libsource (lib "eagle-import") (part "2N7000"))
    )
    (comp (ref "R17")
      (value "10k")
      (footprint "eagle-import:R_P2INCH")
      (libsource (lib "eagle-import") (part "R_P2INCH"))
    )
    (comp (ref "R18")
      (value "10k")
      (footprint "eagle-import:R_P2INCH")
      (libsource (lib "eagle-import") (part "R_P2INCH"))
    )
    (comp (ref "R19")
      (value "10k")
      (footprint "eagle-import:R_P2INCH")
      (libsource (lib "eagle-import") (part "R_P2INCH"))
    )
    (comp (ref "R20")
      (value "10k")
      (footprint "eagle-import:R_P2INCH")
      (libsource (lib "eagle-import") (part "R_P2INCH"))
    )
    (comp (ref "R21")
      (value "10k")
      (footprint "eagle-import:R_P2INCH")
      (libsource (lib "eagle-import") (part "R_P2INCH"))
    )
    (comp (ref "R22")
      (value "10k")
      (footprint "eagle-import:R_P2INCH")
      (libsource (lib "eagle-import") (part "R_P2INCH"))
    )
    (comp (ref "R23")
      (value "10k")
      (footprint "eagle-import:R_P2INCH")
      (libsource (lib "eagle-import") (part "R_P2INCH"))
    )
    (comp (ref "R24")
      (value "10k")
      (footprint "eagle-import:R_P2INCH")
      (libsource (lib "eagle-import") (part "R_P2INCH"))
    )
    (comp (ref "R26")
      (value "10k")
      (footprint "eagle-import:R_P2INCH")
      (libsource (lib "eagle-import") (part "R_P2INCH"))
    )
  )
  (nets
    (net (code "1") (name "+5V") (class "Default")
      (node (ref "C1") (pin "1") (pinfunction "1_1") (pintype "passive"))
      (node (ref "C2") (pin "1") (pinfunction "1_1") (pintype "passive"))
      (node (ref "C3") (pin "1") (pinfunction "1_1") (pintype "passive"))
      (node (ref "C4") (pin "1") (pinfunction "1_1") (pintype "passive"))
      (node (ref "C5") (pin "A") (pinfunction "A_A") (pintype "passive"))
      (node (ref "D1") (pin "A") (pinfunction "A_A") (pintype "passive"))
      (node (ref "D10") (pin "A") (pinfunction "A_A") (pintype "passive"))
      (node (ref "D11") (pin "A") (pinfunction "A_A") (pintype "passive"))
      (node (ref "D12") (pin "A") (pinfunction "A_A") (pintype "passive"))
      (node (ref "D13") (pin "A") (pinfunction "A_A") (pintype "passive"))
      (node (ref "D14") (pin "A") (pinfunction "A_A") (pintype "passive"))
      (node (ref "D15") (pin "A") (pinfunction "A_A") (pintype "passive"))
      (node (ref "D16") (pin "A") (pinfunction "A_A") (pintype "passive"))
      (node (ref "D17") (pin "A") (pinfunction "A_A") (pintype "passive"))
      (node (ref "D18") (pin "A") (pinfunction "A_A") (pintype "passive"))
      (node (ref "D19") (pin "A") (pinfunction "A_A") (pintype "passive"))
      (node (ref "D2") (pin "A") (pinfunction "A_A") (pintype "passive"))
      (node (ref "D20") (pin "A") (pinfunction "A_A") (pintype "passive"))
      (node (ref "D21") (pin "A") (pinfunction "A_A") (pintype "passive"))
      (node (ref "D3") (pin "A") (pinfunction "A_A") (pintype "passive"))
      (node (ref "D4") (pin "A") (pinfunction "A_A") (pintype "passive"))
      (node (ref "D5") (pin "A") (pinfunction "A_A") (pintype "passive"))
      (node (ref "D6") (pin "A") (pinfunction "A_A") (pintype "passive"))
      (node (ref "D7") (pin "A") (pinfunction "A_A") (pintype "passive"))
      (node (ref "D8") (pin "A") (pinfunction "A_A") (pintype "passive"))
      (node (ref "D9") (pin "A") (pinfunction "A_A") (pintype "passive"))
      (node (ref "PP1") (pin "1") (pinfunction "P$1_1") (pintype "bidirectional"))
      (node (ref "R1") (pin "2") (pinfunction "2_2") (pintype "passive"))
      (node (ref "R10") (pin "2") (pinfunction "2_2") (pintype "passive"))
      (node (ref "R11") (pin "2") (pinfunction "2_2") (pintype "passive"))
      (node (ref "R12") (pin "2") (pinfunction "2_2") (pintype "passive"))
      (node (ref "R13") (pin "2") (pinfunction "2_2") (pintype "passive"))
      (node (ref "R14") (pin "2") (pinfunction "2_2") (pintype "passive"))
      (node (ref "R15") (pin "2") (pinfunction "2_2") (pintype "passive"))
      (node (ref "R16") (pin "2") (pinfunction "2_2") (pintype "passive"))
      (node (ref "R17") (pin "2") (pinfunction "2_2") (pintype "passive"))
      (node (ref "R18") (pin "2") (pinfunction "2_2") (pintype "passive"))
      (node (ref "R19") (pin "2") (pinfunction "2_2") (pintype "passive"))
      (node (ref "R2") (pin "2") (pinfunction "2_2") (pintype "passive"))
      (node (ref "R20") (pin "2") (pinfunction "2_2") (pintype "passive"))
      (node (ref "R21") (pin "2") (pinfunction "2_2") (pintype "passive"))
      (node (ref "R22") (pin "2") (pinfunction "2_2") (pintype "passive"))
      (node (ref "R23") (pin "2") (pinfunction "2_2") (pintype "passive"))
      (node (ref "R24") (pin "2") (pinfunction "2_2") (pintype "passive"))
      (node (ref "R25") (pin "2") (pinfunction "2_2") (pintype "passive"))
      (node (ref "R26") (pin "2") (pinfunction "2_2") (pintype "passive"))
      (node (ref "R3") (pin "2") (pinfunction "2_2") (pintype "passive"))
      (node (ref "R31") (pin "2") (pinfunction "2_2") (pintype "passive"))
      (node (ref "R33") (pin "2") (pinfunction "2_2") (pintype "passive"))
      (node (ref "R35") (pin "2") (pinfunction "2_2") (pintype "passive"))
      (node (ref "R37") (pin "2") (pinfunction "2_2") (pintype "passive"))
      (node (ref "R39") (pin "2") (pinfunction "2_2") (pintype "passive"))
      (node (ref "R4") (pin "2") (pinfunction "2_2") (pintype "passive"))
      (node (ref "R41") (pin "2") (pinfunction "2_2") (pintype "passive"))
      (node (ref "R43") (pin "2") (pinfunction "2_2") (pintype "passive"))
      (node (ref "R45") (pin "2") (pinfunction "2_2") (pintype "passive"))
      (node (ref "R47") (pin "2") (pinfunction "2_2") (pintype "passive"))
      (node (ref "R49") (pin "2") (pinfunction "2_2") (pintype "passive"))
      (node (ref "R5") (pin "2") (pinfunction "2_2") (pintype "passive"))
      (node (ref "R51") (pin "2") (pinfunction "2_2") (pintype "passive"))
      (node (ref "R53") (pin "2") (pinfunction "2_2") (pintype "passive"))
      (node (ref "R55") (pin "2") (pinfunction "2_2") (pintype "passive"))
      (node (ref "R57") (pin "2") (pinfunction "2_2") (pintype "passive"))
      (node (ref "R59") (pin "2") (pinfunction "2_2") (pintype "passive"))
      (node (ref "R6") (pin "2") (pinfunction "2_2") (pintype "passive"))
      (node (ref "R61") (pin "2") (pinfunction "2_2") (pintype "passive"))
      (node (ref "R64") (pin "2") (pinfunction "2_2") (pintype "passive"))
      (node (ref "R7") (pin "2") (pinfunction "2_2") (pintype "passive"))
      (node (ref "R8") (pin "2") (pinfunction "2_2") (pintype "passive"))
      (node (ref "R9") (pin "2") (pinfunction "2_2") (pintype "passive"))
    )
    (net (code "2") (name "D0") (class "Default")
      (node (ref "Q2") (pin "D") (pinfunction "D_D") (pintype "passive"))
      (node (ref "Q34") (pin "G") (pinfunction "G_G") (pintype "passive"))
      (node (ref "Q36") (pin "G") (pinfunction "G_G") (pintype "passive"))
      (node (ref "Q38") (pin "G") (pinfunction "G_G") (pintype "passive"))
      (node (ref "Q40") (pin "G") (pinfunction "G_G") (pintype "passive"))
      (node (ref "Q66") (pin "G") (pinfunction "G_G") (pintype "passive"))
      (node (ref "Q68") (pin "G") (pinfunction "G_G") (pintype "passive"))
      (node (ref "Q70") (pin "G") (pinfunction "G_G") (pintype "passive"))
      (node (ref "Q72") (pin "G") (pinfunction "G_G") (pintype "passive"))
      (node (ref "R2") (pin "1") (pinfunction "1_1") (pintype "passive"))
    )
    (net (code "3") (name "D0_N") (class "Default")
      (node (ref "Q1") (pin "D") (pinfunction "D_D") (pintype "passive"))
      (node (ref "Q2") (pin "G") (pinfunction "G_G") (pintype "passive"))
      (node (ref "Q33") (pin "G") (pinfunction "G_G") (pintype "passive"))
      (node (ref "Q35") (pin "G") (pinfunction "G_G") (pintype "passive"))
      (node (ref "Q37") (pin "G") (pinfunction "G_G") (pintype "passive"))
      (node (ref "Q39") (pin "G") (pinfunction "G_G") (pintype "passive"))
      (node (ref "Q65") (pin "G") (pinfunction "G_G") (pintype "passive"))
      (node (ref "Q67") (pin "G") (pinfunction "G_G") (pintype "passive"))
      (node (ref "Q69") (pin "G") (pinfunction "G_G") (pintype "passive"))
      (node (ref "Q71") (pin "G") (pinfunction "G_G") (pintype "passive"))
      (node (ref "R1") (pin "1") (pinfunction "1_1") (pintype "passive"))
      (node (ref "R27") (pin "1") (pinfunction "1_1") (pintype "passive"))
    )
    (net (code "4") (name "D1") (class "Default")
      (node (ref "Q17") (pin "G") (pinfunction "G_G") (pintype "passive"))
      (node (ref "Q20") (pin "G") (pinfunction "G_G") (pintype "passive"))
      (node (ref "Q29") (pin "G") (pinfunction "G_G") (pintype "passive"))
      (node (ref "Q32") (pin "G") (pinfunction "G_G") (pintype "passive"))
      (node (ref "Q4") (pin "D") (pinfunction "D_D") (pintype "passive"))
      (node (ref "Q49") (pin "G") (pinfunction "G_G") (pintype "passive"))
      (node (ref "Q52") (pin "G") (pinfunction "G_G") (pintype "passive"))
      (node (ref "Q61") (pin "G") (pinfunction "G_G") (pintype "passive"))
      (node (ref "Q64") (pin "G") (pinfunction "G_G") (pintype "passive"))
      (node (ref "R4") (pin "1") (pinfunction "1_1") (pintype "passive"))
    )
    (net (code "5") (name "D1_N") (class "Default")
      (node (ref "Q11") (pin "G") (pinfunction "G_G") (pintype "passive"))
      (node (ref "Q14") (pin "G") (pinfunction "G_G") (pintype "passive"))
      (node (ref "Q23") (pin "G") (pinfunction "G_G") (pintype "passive"))
      (node (ref "Q26") (pin "G") (pinfunction "G_G") (pintype "passive"))
      (node (ref "Q3") (pin "D") (pinfunction "D_D") (pintype "passive"))
      (node (ref "Q4") (pin "G") (pinfunction "G_G") (pintype "passive"))
      (node (ref "Q43") (pin "G") (pinfunction "G_G") (pintype "passive"))
      (node (ref "Q46") (pin "G") (pinfunction "G_G") (pintype "passive"))
      (node (ref "Q55") (pin "G") (pinfunction "G_G") (pintype "passive"))
      (node (ref "Q58") (pin "G") (pinfunction "G_G") (pintype "passive"))
      (node (ref "R28") (pin "1") (pinfunction "1_1") (pintype "passive"))
      (node (ref "R3") (pin "1") (pinfunction "1_1") (pintype "passive"))
    )
    (net (code "6") (name "D2") (class "Default")
      (node (ref "Q22") (pin "G") (pinfunction "G_G") (pintype "passive"))
      (node (ref "Q25") (pin "G") (pinfunction "G_G") (pintype "passive"))
      (node (ref "Q28") (pin "G") (pinfunction "G_G") (pintype "passive"))
      (node (ref "Q31") (pin "G") (pinfunction "G_G") (pintype "passive"))
      (node (ref "Q54") (pin "G") (pinfunction "G_G") (pintype "passive"))
      (node (ref "Q57") (pin "G") (pinfunction "G_G") (pintype "passive"))
      (node (ref "Q6") (pin "D") (pinfunction "D_D") (pintype "passive"))
      (node (ref "Q60") (pin "G") (pinfunction "G_G") (pintype "passive"))
      (node (ref "Q63") (pin "G") (pinfunction "G_G") (pintype "passive"))
      (node (ref "R6") (pin "1") (pinfunction "1_1") (pintype "passive"))
    )
    (net (code "7") (name "D2_N") (class "Default")
      (node (ref "Q10") (pin "G") (pinfunction "G_G") (pintype "passive"))
      (node (ref "Q13") (pin "G") (pinfunction "G_G") (pintype "passive"))
      (node (ref "Q16") (pin "G") (pinfunction "G_G") (pintype "passive"))
      (node (ref "Q19") (pin "G") (pinfunction "G_G") (pintype "passive"))
      (node (ref "Q42") (pin "G") (pinfunction "G_G") (pintype "passive"))
      (node (ref "Q45") (pin "G") (pinfunction "G_G") (pintype "passive"))
      (node (ref "Q48") (pin "G") (pinfunction "G_G") (pintype "passive"))
      (node (ref "Q5") (pin "D") (pinfunction "D_D") (pintype "passive"))
      (node (ref "Q51") (pin "G") (pinfunction "G_G") (pintype "passive"))
      (node (ref "Q6") (pin "G") (pinfunction "G_G") (pintype "passive"))
      (node (ref "R29") (pin "1") (pinfunction "1_1") (pintype "passive"))
      (node (ref "R5") (pin "1") (pinfunction "1_1") (pintype "passive"))
    )
    (net (code "8") (name "D3") (class "Default")
      (node (ref "Q41") (pin "G") (pinfunction "G_G") (pintype "passive"))
      (node (ref "Q44") (pin "G") (pinfunction "G_G") (pintype "passive"))
      (node (ref "Q47") (pin "G") (pinfunction "G_G") (pintype "passive"))
      (node (ref "Q50") (pin "G") (pinfunction "G_G") (pintype "passive"))
      (node (ref "Q53") (pin "G") (pinfunction "G_G") (pintype "passive"))
      (node (ref "Q56") (pin "G") (pinfunction "G_G") (pintype "passive"))
      (node (ref "Q59") (pin "G") (pinfunction "G_G") (pintype "passive"))
      (node (ref "Q62") (pin "G") (pinfunction "G_G") (pintype "passive"))
      (node (ref "Q8") (pin "D") (pinfunction "D_D") (pintype "passive"))
      (node (ref "R8") (pin "1") (pinfunction "1_1") (pintype "passive"))
    )
    (net (code "9") (name "D3_N") (class "Default")
      (node (ref "Q12") (pin "G") (pinfunction "G_G") (pintype "passive"))
      (node (ref "Q15") (pin "G") (pinfunction "G_G") (pintype "passive"))
      (node (ref "Q18") (pin "G") (pinfunction "G_G") (pintype "passive"))
      (node (ref "Q21") (pin "G") (pinfunction "G_G") (pintype "passive"))
      (node (ref "Q24") (pin "G") (pinfunction "G_G") (pintype "passive"))
      (node (ref "Q27") (pin "G") (pinfunction "G_G") (pintype "passive"))
      (node (ref "Q30") (pin "G") (pinfunction "G_G") (pintype "passive"))
      (node (ref "Q7") (pin "D") (pinfunction "D_D") (pintype "passive"))
      (node (ref "Q8") (pin "G") (pinfunction "G_G") (pintype "passive"))
      (node (ref "Q9") (pin "G") (pinfunction "G_G") (pintype "passive"))
      (node (ref "R30") (pin "1") (pinfunction "1_1") (pintype "passive"))
      (node (ref "R7") (pin "1") (pinfunction "1_1") (pintype "passive"))
    )
    (net (code "10") (name "DIN0") (class "Default")
      (node (ref "Q1") (pin "G") (pinfunction "G_G") (pintype "passive"))
      (node (ref "TP2") (pin "P$1") (pinfunction "P$1_P$1") (pintype "bidirectional"))
    )
    (net (code "11") (name "DIN1") (class "Default")
      (node (ref "Q3") (pin "G") (pinfunction "G_G") (pintype "passive"))
      (node (ref "TP3") (pin "P$1") (pinfunction "P$1_P$1") (pintype "bidirectional"))
    )
    (net (code "12") (name "DIN2") (class "Default")
      (node (ref "Q5") (pin "G") (pinfunction "G_G") (pintype "passive"))
      (node (ref "TP4") (pin "P$1") (pinfunction "P$1_P$1") (pintype "bidirectional"))
    )
    (net (code "13") (name "DIN3") (class "Default")
      (node (ref "Q7") (pin "G") (pinfunction "G_G") (pintype "passive"))
      (node (ref "TP5") (pin "P$1") (pinfunction "P$1_P$1") (pintype "bidirectional"))
    )
    (net (code "14") (name "EN") (class "Default")
      (node (ref "Q73") (pin "G") (pinfunction "G_G") (pintype "passive"))
      (node (ref "Q74") (pin "G") (pinfunction "G_G") (pintype "passive"))
      (node (ref "Q92") (pin "D") (pinfunction "D_D") (pintype "passive"))
      (node (ref "R64") (pin "1") (pinfunction "1_1") (pintype "passive"))
    )
    (net (code "15") (name "EN_IN") (class "Default")
      (node (ref "Q91") (pin "G") (pinfunction "G_G") (pintype "passive"))
      (node (ref "TP1") (pin "P$1") (pinfunction "P$1_P$1") (pintype "bidirectional"))
    )
    (net (code "16") (name "EN_N") (class "Default")
      (node (ref "Q91") (pin "D") (pinfunction "D_D") (pintype "passive"))
      (node (ref "Q92") (pin "G") (pinfunction "G_G") (pintype "passive"))
      (node (ref "R63") (pin "1") (pinfunction "1_1") (pintype "passive"))
    )
    (net (code "17") (name "GND") (class "Default")
      (node (ref "C1") (pin "2") (pinfunction "2_2") (pintype "passive"))
      (node (ref "C2") (pin "2") (pinfunction "2_2") (pintype "passive"))
      (node (ref "C3") (pin "2") (pinfunction "2_2") (pintype "passive"))
      (node (ref "C4") (pin "2") (pinfunction "2_2") (pintype "passive"))
      (node (ref "C5") (pin "K") (pinfunction "K_K") (pintype "passive"))
      (node (ref "PP2") (pin "1") (pinfunction "P$1_1") (pintype "bidirectional"))
      (node (ref "Q1") (pin "S") (pinfunction "S_S") (pintype "passive"))
      (node (ref "Q2") (pin "S") (pinfunction "S_S") (pintype "passive"))
      (node (ref "Q3") (pin "S") (pinfunction "S_S") (pintype "passive"))
      (node (ref "Q4") (pin "S") (pinfunction "S_S") (pintype "passive"))
      (node (ref "Q5") (pin "S") (pinfunction "S_S") (pintype "passive"))
      (node (ref "Q6") (pin "S") (pinfunction "S_S") (pintype "passive"))
      (node (ref "Q7") (pin "S") (pinfunction "S_S") (pintype "passive"))
      (node (ref "Q73") (pin "S") (pinfunction "S_S") (pintype "passive"))
      (node (ref "Q74") (pin "S") (pinfunction "S_S") (pintype "passive"))
      (node (ref "Q75") (pin "S") (pinfunction "S_S") (pintype "passive"))
      (node (ref "Q76") (pin "S") (pinfunction "S_S") (pintype "passive"))
      (node (ref "Q77") (pin "S") (pinfunction "S_S") (pintype "passive"))
      (node (ref "Q78") (pin "S") (pinfunction "S_S") (pintype "passive"))
      (node (ref "Q79") (pin "S") (pinfunction "S_S") (pintype "passive"))
      (node (ref "Q8") (pin "S") (pinfunction "S_S") (pintype "passive"))
      (node (ref "Q80") (pin "S") (pinfunction "S_S") (pintype "passive"))
      (node (ref "Q81") (pin "S") (pinfunction "S_S") (pintype "passive"))
      (node (ref "Q82") (pin "S") (pinfunction "S_S") (pintype "passive"))
      (node (ref "Q83") (pin "S") (pinfunction "S_S") (pintype "passive"))
      (node (ref "Q84") (pin "S") (pinfunction "S_S") (pintype "passive"))
      (node (ref "Q85") (pin "S") (pinfunction "S_S") (pintype "passive"))
      (node (ref "Q86") (pin "S") (pinfunction "S_S") (pintype "passive"))
      (node (ref "Q87") (pin "S") (pinfunction "S_S") (pintype "passive"))
      (node (ref "Q88") (pin "S") (pinfunction "S_S") (pintype "passive"))
      (node (ref "Q89") (pin "S") (pinfunction "S_S") (pintype "passive"))
      (node (ref "Q90") (pin "S") (pinfunction "S_S") (pintype "passive"))
      (node (ref "Q91") (pin "S") (pinfunction "S_S") (pintype "passive"))
      (node (ref "Q92") (pin "S") (pinfunction "S_S") (pintype "passive"))
    )
    (net (code "18") (name "Net-(D1-C)") (class "Default")
      (node (ref "D1") (pin "K") (pinfunction "C_K") (pintype "passive"))
      (node (ref "R27") (pin "2") (pinfunction "2_2") (pintype "passive"))
    )
    (net (code "19") (name "Net-(D2-C)") (class "Default")
      (node (ref "D2") (pin "K") (pinfunction "C_K") (pintype "passive"))
      (node (ref "R28") (pin "2") (pinfunction "2_2") (pintype "passive"))
    )
    (net (code "20") (name "Net-(D3-C)") (class "Default")
      (node (ref "D3") (pin "K") (pinfunction "C_K") (pintype "passive"))
      (node (ref "R29") (pin "2") (pinfunction "2_2") (pintype "passive"))
    )
    (net (code "21") (name "Net-(D4-C)") (class "Default")
      (node (ref "D4") (pin "K") (pinfunction "C_K") (pintype "passive"))
      (node (ref "R30") (pin "2") (pinfunction "2_2") (pintype "passive"))
    )
    (net (code "22") (name "Net-(D5-C)") (class "Default")
      (node (ref "D5") (pin "K") (pinfunction "C_K") (pintype "passive"))
      (node (ref "R32") (pin "2") (pinfunction "2_2") (pintype "passive"))
    )
    (net (code "23") (name "Net-(D6-C)") (class "Default")
      (node (ref "D6") (pin "K") (pinfunction "C_K") (pintype "passive"))
      (node (ref "R34") (pin "2") (pinfunction "2_2") (pintype "passive"))
    )
    (net (code "24") (name "Net-(D7-C)") (class "Default")
      (node (ref "D7") (pin "K") (pinfunction "C_K") (pintype "passive"))
      (node (ref "R36") (pin "2") (pinfunction "2_2") (pintype "passive"))
    )
    (net (code "25") (name "Net-(D8-C)") (class "Default")
      (node (ref "D8") (pin "K") (pinfunction "C_K") (pintype "passive"))
      (node (ref "R38") (pin "2") (pinfunction "2_2") (pintype "passive"))
    )
    (net (code "26") (name "Net-(D9-C)") (class "Default")
      (node (ref "D9") (pin "K") (pinfunction "C_K") (pintype "passive"))
      (node (ref "R40") (pin "2") (pinfunction "2_2") (pintype "passive"))
    )
    (net (code "27") (name "Net-(D10-C)") (class "Default")
      (node (ref "D10") (pin "K") (pinfunction "C_K") (pintype "passive"))
      (node (ref "R42") (pin "2") (pinfunction "2_2") (pintype "passive"))
    )
    (net (code "28") (name "Net-(D11-C)") (class "Default")
      (node (ref "D11") (pin "K") (pinfunction "C_K") (pintype "passive"))
      (node (ref "R44") (pin "2") (pinfunction "2_2") (pintype "passive"))
    )
    (net (code "29") (name "Net-(D12-C)") (class "Default")
      (node (ref "D12") (pin "K") (pinfunction "C_K") (pintype "passive"))
      (node (ref "R46") (pin "2") (pinfunction "2_2") (pintype "passive"))
    )
    (net (code "30") (name "Net-(D13-C)") (class "Default")
      (node (ref "D13") (pin "K") (pinfunction "C_K") (pintype "passive"))
      (node (ref "R48") (pin "2") (pinfunction "2_2") (pintype "passive"))
    )
    (net (code "31") (name "Net-(D14-C)") (class "Default")
      (node (ref "D14") (pin "K") (pinfunction "C_K") (pintype "passive"))
      (node (ref "R50") (pin "2") (pinfunction "2_2") (pintype "passive"))
    )
    (net (code "32") (name "Net-(D15-C)") (class "Default")
      (node (ref "D15") (pin "K") (pinfunction "C_K") (pintype "passive"))
      (node (ref "R52") (pin "2") (pinfunction "2_2") (pintype "passive"))
    )
    (net (code "33") (name "Net-(D16-C)") (class "Default")
      (node (ref "D16") (pin "K") (pinfunction "C_K") (pintype "passive"))
      (node (ref "R54") (pin "2") (pinfunction "2_2") (pintype "passive"))
    )
    (net (code "34") (name "Net-(D17-C)") (class "Default")
      (node (ref "D17") (pin "K") (pinfunction "C_K") (pintype "passive"))
      (node (ref "R56") (pin "2") (pinfunction "2_2") (pintype "passive"))
    )
    (net (code "35") (name "Net-(D18-C)") (class "Default")
      (node (ref "D18") (pin "K") (pinfunction "C_K") (pintype "passive"))
      (node (ref "R58") (pin "2") (pinfunction "2_2") (pintype "passive"))
    )
    (net (code "36") (name "Net-(D19-C)") (class "Default")
      (node (ref "D19") (pin "K") (pinfunction "C_K") (pintype "passive"))
      (node (ref "R60") (pin "2") (pinfunction "2_2") (pintype "passive"))
    )
    (net (code "37") (name "Net-(D20-C)") (class "Default")
      (node (ref "D20") (pin "K") (pinfunction "C_K") (pintype "passive"))
      (node (ref "R62") (pin "2") (pinfunction "2_2") (pintype "passive"))
    )
    (net (code "38") (name "Net-(D21-C)") (class "Default")
      (node (ref "D21") (pin "K") (pinfunction "C_K") (pintype "passive"))
      (node (ref "R63") (pin "2") (pinfunction "2_2") (pintype "passive"))
    )
    (net (code "39") (name "Net-(Q10-PadD)") (class "Default")
      (node (ref "Q10") (pin "D") (pinfunction "D_D") (pintype "passive"))
      (node (ref "Q9") (pin "S") (pinfunction "S_S") (pintype "passive"))
    )
    (net (code "40") (name "Net-(Q10-PadS)") (class "Default")
      (node (ref "Q10") (pin "S") (pinfunction "S_S") (pintype "passive"))
      (node (ref "Q11") (pin "D") (pinfunction "D_D") (pintype "passive"))
    )
    (net (code "41") (name "Net-(Q11-PadS)") (class "Default")
      (node (ref "Q11") (pin "S") (pinfunction "S_S") (pintype "passive"))
      (node (ref "Q33") (pin "D") (pinfunction "D_D") (pintype "passive"))
    )
    (net (code "42") (name "Net-(Q12-PadS)") (class "Default")
      (node (ref "Q12") (pin "S") (pinfunction "S_S") (pintype "passive"))
      (node (ref "Q13") (pin "D") (pinfunction "D_D") (pintype "passive"))
    )
    (net (code "43") (name "Net-(Q13-PadS)") (class "Default")
      (node (ref "Q13") (pin "S") (pinfunction "S_S") (pintype "passive"))
      (node (ref "Q14") (pin "D") (pinfunction "D_D") (pintype "passive"))
    )
    (net (code "44") (name "Net-(Q14-PadS)") (class "Default")
      (node (ref "Q14") (pin "S") (pinfunction "S_S") (pintype "passive"))
      (node (ref "Q34") (pin "D") (pinfunction "D_D") (pintype "passive"))
    )
    (net (code "45") (name "Net-(Q15-PadS)") (class "Default")
      (node (ref "Q15") (pin "S") (pinfunction "S_S") (pintype "passive"))
      (node (ref "Q16") (pin "D") (pinfunction "D_D") (pintype "passive"))
    )
    (net (code "46") (name "Net-(Q16-PadS)") (class "Default")
      (node (ref "Q16") (pin "S") (pinfunction "S_S") (pintype "passive"))
      (node (ref "Q17") (pin "D") (pinfunction "D_D") (pintype "passive"))
    )
    (net (code "47") (name "Net-(Q17-PadS)") (class "Default")
      (node (ref "Q17") (pin "S") (pinfunction "S_S") (pintype "passive"))
      (node (ref "Q35") (pin "D") (pinfunction "D_D") (pintype "passive"))
    )
    (net (code "48") (name "Net-(Q18-PadS)") (class "Default")
      (node (ref "Q18") (pin "S") (pinfunction "S_S") (pintype "passive"))
      (node (ref "Q19") (pin "D") (pinfunction "D_D") (pintype "passive"))
    )
    (net (code "49") (name "Net-(Q19-PadS)") (class "Default")
      (node (ref "Q19") (pin "S") (pinfunction "S_S") (pintype "passive"))
      (node (ref "Q20") (pin "D") (pinfunction "D_D") (pintype "passive"))
    )
    (net (code "50") (name "Net-(Q20-PadS)") (class "Default")
      (node (ref "Q20") (pin "S") (pinfunction "S_S") (pintype "passive"))
      (node (ref "Q36") (pin "D") (pinfunction "D_D") (pintype "passive"))
    )
    (net (code "51") (name "Net-(Q21-PadS)") (class "Default")
      (node (ref "Q21") (pin "S") (pinfunction "S_S") (pintype "passive"))
      (node (ref "Q22") (pin "D") (pinfunction "D_D") (pintype "passive"))
    )
    (net (code "52") (name "Net-(Q22-PadS)") (class "Default")
      (node (ref "Q22") (pin "S") (pinfunction "S_S") (pintype "passive"))
      (node (ref "Q23") (pin "D") (pinfunction "D_D") (pintype "passive"))
    )
    (net (code "53") (name "Net-(Q23-PadS)") (class "Default")
      (node (ref "Q23") (pin "S") (pinfunction "S_S") (pintype "passive"))
      (node (ref "Q37") (pin "D") (pinfunction "D_D") (pintype "passive"))
    )
    (net (code "54") (name "Net-(Q24-PadS)") (class "Default")
      (node (ref "Q24") (pin "S") (pinfunction "S_S") (pintype "passive"))
      (node (ref "Q25") (pin "D") (pinfunction "D_D") (pintype "passive"))
    )
    (net (code "55") (name "Net-(Q25-PadS)") (class "Default")
      (node (ref "Q25") (pin "S") (pinfunction "S_S") (pintype "passive"))
      (node (ref "Q26") (pin "D") (pinfunction "D_D") (pintype "passive"))
    )
    (net (code "56") (name "Net-(Q26-PadS)") (class "Default")
      (node (ref "Q26") (pin "S") (pinfunction "S_S") (pintype "passive"))
      (node (ref "Q38") (pin "D") (pinfunction "D_D") (pintype "passive"))
    )
    (net (code "57") (name "Net-(Q27-PadS)") (class "Default")
      (node (ref "Q27") (pin "S") (pinfunction "S_S") (pintype "passive"))
      (node (ref "Q28") (pin "D") (pinfunction "D_D") (pintype "passive"))
    )
    (net (code "58") (name "Net-(Q28-PadS)") (class "Default")
      (node (ref "Q28") (pin "S") (pinfunction "S_S") (pintype "passive"))
      (node (ref "Q29") (pin "D") (pinfunction "D_D") (pintype "passive"))
    )
    (net (code "59") (name "Net-(Q29-PadS)") (class "Default")
      (node (ref "Q29") (pin "S") (pinfunction "S_S") (pintype "passive"))
      (node (ref "Q39") (pin "D") (pinfunction "D_D") (pintype "passive"))
    )
    (net (code "60") (name "Net-(Q30-PadS)") (class "Default")
      (node (ref "Q30") (pin "S") (pinfunction "S_S") (pintype "passive"))
      (node (ref "Q31") (pin "D") (pinfunction "D_D") (pintype "passive"))
    )
    (net (code "61") (name "Net-(Q31-PadS)") (class "Default")
      (node (ref "Q31") (pin "S") (pinfunction "S_S") (pintype "passive"))
      (node (ref "Q32") (pin "D") (pinfunction "D_D") (pintype "passive"))
    )
    (net (code "62") (name "Net-(Q32-PadS)") (class "Default")
      (node (ref "Q32") (pin "S") (pinfunction "S_S") (pintype "passive"))
      (node (ref "Q40") (pin "D") (pinfunction "D_D") (pintype "passive"))
    )
    (net (code "63") (name "Net-(Q33-PadS)") (class "Default")
      (node (ref "Q33") (pin "S") (pinfunction "S_S") (pintype "passive"))
      (node (ref "Q34") (pin "S") (pinfunction "S_S") (pintype "passive"))
      (node (ref "Q35") (pin "S") (pinfunction "S_S") (pintype "passive"))
      (node (ref "Q36") (pin "S") (pinfunction "S_S") (pintype "passive"))
      (node (ref "Q37") (pin "S") (pinfunction "S_S") (pintype "passive"))
      (node (ref "Q38") (pin "S") (pinfunction "S_S") (pintype "passive"))
      (node (ref "Q39") (pin "S") (pinfunction "S_S") (pintype "passive"))
      (node (ref "Q40") (pin "S") (pinfunction "S_S") (pintype "passive"))
      (node (ref "Q73") (pin "D") (pinfunction "D_D") (pintype "passive"))
      (node (ref "R25") (pin "1") (pinfunction "1_1") (pintype "passive"))
    )
    (net (code "64") (name "Net-(Q41-PadS)") (class "Default")
      (node (ref "Q41") (pin "S") (pinfunction "S_S") (pintype "passive"))
      (node (ref "Q42") (pin "D") (pinfunction "D_D") (pintype "passive"))
    )
    (net (code "65") (name "Net-(Q42-PadS)") (class "Default")
      (node (ref "Q42") (pin "S") (pinfunction "S_S") (pintype "passive"))
      (node (ref "Q43") (pin "D") (pinfunction "D_D") (pintype "passive"))
    )
    (net (code "66") (name "Net-(Q43-PadS)") (class "Default")
      (node (ref "Q43") (pin "S") (pinfunction "S_S") (pintype "passive"))
      (node (ref "Q65") (pin "D") (pinfunction "D_D") (pintype "passive"))
    )
    (net (code "67") (name "Net-(Q44-PadS)") (class "Default")
      (node (ref "Q44") (pin "S") (pinfunction "S_S") (pintype "passive"))
      (node (ref "Q45") (pin "D") (pinfunction "D_D") (pintype "passive"))
    )
    (net (code "68") (name "Net-(Q45-PadS)") (class "Default")
      (node (ref "Q45") (pin "S") (pinfunction "S_S") (pintype "passive"))
      (node (ref "Q46") (pin "D") (pinfunction "D_D") (pintype "passive"))
    )
    (net (code "69") (name "Net-(Q46-PadS)") (class "Default")
      (node (ref "Q46") (pin "S") (pinfunction "S_S") (pintype "passive"))
      (node (ref "Q66") (pin "D") (pinfunction "D_D") (pintype "passive"))
    )
    (net (code "70") (name "Net-(Q47-PadS)") (class "Default")
      (node (ref "Q47") (pin "S") (pinfunction "S_S") (pintype "passive"))
      (node (ref "Q48") (pin "D") (pinfunction "D_D") (pintype "passive"))
    )
    (net (code "71") (name "Net-(Q48-PadS)") (class "Default")
      (node (ref "Q48") (pin "S") (pinfunction "S_S") (pintype "passive"))
      (node (ref "Q49") (pin "D") (pinfunction "D_D") (pintype "passive"))
    )
    (net (code "72") (name "Net-(Q49-PadS)") (class "Default")
      (node (ref "Q49") (pin "S") (pinfunction "S_S") (pintype "passive"))
      (node (ref "Q67") (pin "D") (pinfunction "D_D") (pintype "passive"))
    )
    (net (code "73") (name "Net-(Q50-PadS)") (class "Default")
      (node (ref "Q50") (pin "S") (pinfunction "S_S") (pintype "passive"))
      (node (ref "Q51") (pin "D") (pinfunction "D_D") (pintype "passive"))
    )
    (net (code "74") (name "Net-(Q51-PadS)") (class "Default")
      (node (ref "Q51") (pin "S") (pinfunction "S_S") (pintype "passive"))
      (node (ref "Q52") (pin "D") (pinfunction "D_D") (pintype "passive"))
    )
    (net (code "75") (name "Net-(Q52-PadS)") (class "Default")
      (node (ref "Q52") (pin "S") (pinfunction "S_S") (pintype "passive"))
      (node (ref "Q68") (pin "D") (pinfunction "D_D") (pintype "passive"))
    )
    (net (code "76") (name "Net-(Q53-PadS)") (class "Default")
      (node (ref "Q53") (pin "S") (pinfunction "S_S") (pintype "passive"))
      (node (ref "Q54") (pin "D") (pinfunction "D_D") (pintype "passive"))
    )
    (net (code "77") (name "Net-(Q54-PadS)") (class "Default")
      (node (ref "Q54") (pin "S") (pinfunction "S_S") (pintype "passive"))
      (node (ref "Q55") (pin "D") (pinfunction "D_D") (pintype "passive"))
    )
    (net (code "78") (name "Net-(Q55-PadS)") (class "Default")
      (node (ref "Q55") (pin "S") (pinfunction "S_S") (pintype "passive"))
      (node (ref "Q69") (pin "D") (pinfunction "D_D") (pintype "passive"))
    )
    (net (code "79") (name "Net-(Q56-PadS)") (class "Default")
      (node (ref "Q56") (pin "S") (pinfunction "S_S") (pintype "passive"))
      (node (ref "Q57") (pin "D") (pinfunction "D_D") (pintype "passive"))
    )
    (net (code "80") (name "Net-(Q57-PadS)") (class "Default")
      (node (ref "Q57") (pin "S") (pinfunction "S_S") (pintype "passive"))
      (node (ref "Q58") (pin "D") (pinfunction "D_D") (pintype "passive"))
    )
    (net (code "81") (name "Net-(Q58-PadS)") (class "Default")
      (node (ref "Q58") (pin "S") (pinfunction "S_S") (pintype "passive"))
      (node (ref "Q70") (pin "D") (pinfunction "D_D") (pintype "passive"))
    )
    (net (code "82") (name "Net-(Q59-PadS)") (class "Default")
      (node (ref "Q59") (pin "S") (pinfunction "S_S") (pintype "passive"))
      (node (ref "Q60") (pin "D") (pinfunction "D_D") (pintype "passive"))
    )
    (net (code "83") (name "Net-(Q60-PadS)") (class "Default")
      (node (ref "Q60") (pin "S") (pinfunction "S_S") (pintype "passive"))
      (node (ref "Q61") (pin "D") (pinfunction "D_D") (pintype "passive"))
    )
    (net (code "84") (name "Net-(Q61-PadS)") (class "Default")
      (node (ref "Q61") (pin "S") (pinfunction "S_S") (pintype "passive"))
      (node (ref "Q71") (pin "D") (pinfunction "D_D") (pintype "passive"))
    )
    (net (code "85") (name "Net-(Q62-PadS)") (class "Default")
      (node (ref "Q62") (pin "S") (pinfunction "S_S") (pintype "passive"))
      (node (ref "Q63") (pin "D") (pinfunction "D_D") (pintype "passive"))
    )
    (net (code "86") (name "Net-(Q63-PadS)") (class "Default")
      (node (ref "Q63") (pin "S") (pinfunction "S_S") (pintype "passive"))
      (node (ref "Q64") (pin "D") (pinfunction "D_D") (pintype "passive"))
    )
    (net (code "87") (name "Net-(Q64-PadS)") (class "Default")
      (node (ref "Q64") (pin "S") (pinfunction "S_S") (pintype "passive"))
      (node (ref "Q72") (pin "D") (pinfunction "D_D") (pintype "passive"))
    )
    (net (code "88") (name "Net-(Q65-PadS)") (class "Default")
      (node (ref "Q65") (pin "S") (pinfunction "S_S") (pintype "passive"))
      (node (ref "Q66") (pin "S") (pinfunction "S_S") (pintype "passive"))
      (node (ref "Q67") (pin "S") (pinfunction "S_S") (pintype "passive"))
      (node (ref "Q68") (pin "S") (pinfunction "S_S") (pintype "passive"))
      (node (ref "Q69") (pin "S") (pinfunction "S_S") (pintype "passive"))
      (node (ref "Q70") (pin "S") (pinfunction "S_S") (pintype "passive"))
      (node (ref "Q71") (pin "S") (pinfunction "S_S") (pintype "passive"))
      (node (ref "Q72") (pin "S") (pinfunction "S_S") (pintype "passive"))
      (node (ref "Q74") (pin "D") (pinfunction "D_D") (pintype "passive"))
      (node (ref "R26") (pin "1") (pinfunction "1_1") (pintype "passive"))
    )
    (net (code "89") (name "S0") (class "Default")
      (node (ref "Q75") (pin "D") (pinfunction "D_D") (pintype "passive"))
      (node (ref "R31") (pin "1") (pinfunction "1_1") (pintype "passive"))
      (node (ref "TP6") (pin "P$1") (pinfunction "P$1_P$1") (pintype "bidirectional"))
    )
    (net (code "90") (name "S0_N") (class "Default")
      (node (ref "Q75") (pin "G") (pinfunction "G_G") (pintype "passive"))
      (node (ref "Q9") (pin "D") (pinfunction "D_D") (pintype "passive"))
      (node (ref "R32") (pin "1") (pinfunction "1_1") (pintype "passive"))
      (node (ref "R9") (pin "1") (pinfunction "1_1") (pintype "passive"))
      (node (ref "TP14") (pin "P$1") (pinfunction "P$1_P$1") (pintype "bidirectional"))
    )
    (net (code "91") (name "S1") (class "Default")
      (node (ref "Q76") (pin "D") (pinfunction "D_D") (pintype "passive"))
      (node (ref "R33") (pin "1") (pinfunction "1_1") (pintype "passive"))
      (node (ref "TP7") (pin "P$1") (pinfunction "P$1_P$1") (pintype "bidirectional"))
    )
    (net (code "92") (name "S1_N") (class "Default")
      (node (ref "Q12") (pin "D") (pinfunction "D_D") (pintype "passive"))
      (node (ref "Q76") (pin "G") (pinfunction "G_G") (pintype "passive"))
      (node (ref "R10") (pin "1") (pinfunction "1_1") (pintype "passive"))
      (node (ref "R34") (pin "1") (pinfunction "1_1") (pintype "passive"))
      (node (ref "TP15") (pin "P$1") (pinfunction "P$1_P$1") (pintype "bidirectional"))
    )
    (net (code "93") (name "S2") (class "Default")
      (node (ref "Q77") (pin "D") (pinfunction "D_D") (pintype "passive"))
      (node (ref "R35") (pin "1") (pinfunction "1_1") (pintype "passive"))
      (node (ref "TP8") (pin "P$1") (pinfunction "P$1_P$1") (pintype "bidirectional"))
    )
    (net (code "94") (name "S2_N") (class "Default")
      (node (ref "Q15") (pin "D") (pinfunction "D_D") (pintype "passive"))
      (node (ref "Q77") (pin "G") (pinfunction "G_G") (pintype "passive"))
      (node (ref "R11") (pin "1") (pinfunction "1_1") (pintype "passive"))
      (node (ref "R36") (pin "1") (pinfunction "1_1") (pintype "passive"))
      (node (ref "TP16") (pin "P$1") (pinfunction "P$1_P$1") (pintype "bidirectional"))
    )
    (net (code "95") (name "S3") (class "Default")
      (node (ref "Q78") (pin "D") (pinfunction "D_D") (pintype "passive"))
      (node (ref "R37") (pin "1") (pinfunction "1_1") (pintype "passive"))
      (node (ref "TP9") (pin "P$1") (pinfunction "P$1_P$1") (pintype "bidirectional"))
    )
    (net (code "96") (name "S3_N") (class "Default")
      (node (ref "Q18") (pin "D") (pinfunction "D_D") (pintype "passive"))
      (node (ref "Q78") (pin "G") (pinfunction "G_G") (pintype "passive"))
      (node (ref "R12") (pin "1") (pinfunction "1_1") (pintype "passive"))
      (node (ref "R38") (pin "1") (pinfunction "1_1") (pintype "passive"))
      (node (ref "TP17") (pin "P$1") (pinfunction "P$1_P$1") (pintype "bidirectional"))
    )
    (net (code "97") (name "S4") (class "Default")
      (node (ref "Q79") (pin "D") (pinfunction "D_D") (pintype "passive"))
      (node (ref "R39") (pin "1") (pinfunction "1_1") (pintype "passive"))
      (node (ref "TP10") (pin "P$1") (pinfunction "P$1_P$1") (pintype "bidirectional"))
    )
    (net (code "98") (name "S4_N") (class "Default")
      (node (ref "Q21") (pin "D") (pinfunction "D_D") (pintype "passive"))
      (node (ref "Q79") (pin "G") (pinfunction "G_G") (pintype "passive"))
      (node (ref "R13") (pin "1") (pinfunction "1_1") (pintype "passive"))
      (node (ref "R40") (pin "1") (pinfunction "1_1") (pintype "passive"))
      (node (ref "TP18") (pin "P$1") (pinfunction "P$1_P$1") (pintype "bidirectional"))
    )
    (net (code "99") (name "S5") (class "Default")
      (node (ref "Q80") (pin "D") (pinfunction "D_D") (pintype "passive"))
      (node (ref "R41") (pin "1") (pinfunction "1_1") (pintype "passive"))
      (node (ref "TP11") (pin "P$1") (pinfunction "P$1_P$1") (pintype "bidirectional"))
    )
    (net (code "100") (name "S5_N") (class "Default")
      (node (ref "Q24") (pin "D") (pinfunction "D_D") (pintype "passive"))
      (node (ref "Q80") (pin "G") (pinfunction "G_G") (pintype "passive"))
      (node (ref "R14") (pin "1") (pinfunction "1_1") (pintype "passive"))
      (node (ref "R42") (pin "1") (pinfunction "1_1") (pintype "passive"))
      (node (ref "TP19") (pin "P$1") (pinfunction "P$1_P$1") (pintype "bidirectional"))
    )
    (net (code "101") (name "S6") (class "Default")
      (node (ref "Q81") (pin "D") (pinfunction "D_D") (pintype "passive"))
      (node (ref "R43") (pin "1") (pinfunction "1_1") (pintype "passive"))
      (node (ref "TP12") (pin "P$1") (pinfunction "P$1_P$1") (pintype "bidirectional"))
    )
    (net (code "102") (name "S6_N") (class "Default")
      (node (ref "Q27") (pin "D") (pinfunction "D_D") (pintype "passive"))
      (node (ref "Q81") (pin "G") (pinfunction "G_G") (pintype "passive"))
      (node (ref "R15") (pin "1") (pinfunction "1_1") (pintype "passive"))
      (node (ref "R44") (pin "1") (pinfunction "1_1") (pintype "passive"))
      (node (ref "TP20") (pin "P$1") (pinfunction "P$1_P$1") (pintype "bidirectional"))
    )
    (net (code "103") (name "S7") (class "Default")
      (node (ref "Q82") (pin "D") (pinfunction "D_D") (pintype "passive"))
      (node (ref "R45") (pin "1") (pinfunction "1_1") (pintype "passive"))
      (node (ref "TP13") (pin "P$1") (pinfunction "P$1_P$1") (pintype "bidirectional"))
    )
    (net (code "104") (name "S7_N") (class "Default")
      (node (ref "Q30") (pin "D") (pinfunction "D_D") (pintype "passive"))
      (node (ref "Q82") (pin "G") (pinfunction "G_G") (pintype "passive"))
      (node (ref "R16") (pin "1") (pinfunction "1_1") (pintype "passive"))
      (node (ref "R46") (pin "1") (pinfunction "1_1") (pintype "passive"))
      (node (ref "TP21") (pin "P$1") (pinfunction "P$1_P$1") (pintype "bidirectional"))
    )
    (net (code "105") (name "S8") (class "Default")
      (node (ref "Q83") (pin "D") (pinfunction "D_D") (pintype "passive"))
      (node (ref "R47") (pin "1") (pinfunction "1_1") (pintype "passive"))
      (node (ref "TP22") (pin "P$1") (pinfunction "P$1_P$1") (pintype "bidirectional"))
    )
    (net (code "106") (name "S8_N") (class "Default")
      (node (ref "Q41") (pin "D") (pinfunction "D_D") (pintype "passive"))
      (node (ref "Q83") (pin "G") (pinfunction "G_G") (pintype "passive"))
      (node (ref "R17") (pin "1") (pinfunction "1_1") (pintype "passive"))
      (node (ref "R48") (pin "1") (pinfunction "1_1") (pintype "passive"))
      (node (ref "TP30") (pin "P$1") (pinfunction "P$1_P$1") (pintype "bidirectional"))
    )
    (net (code "107") (name "S9") (class "Default")
      (node (ref "Q84") (pin "D") (pinfunction "D_D") (pintype "passive"))
      (node (ref "R49") (pin "1") (pinfunction "1_1") (pintype "passive"))
      (node (ref "TP23") (pin "P$1") (pinfunction "P$1_P$1") (pintype "bidirectional"))
    )
    (net (code "108") (name "S9_N") (class "Default")
      (node (ref "Q44") (pin "D") (pinfunction "D_D") (pintype "passive"))
      (node (ref "Q84") (pin "G") (pinfunction "G_G") (pintype "passive"))
      (node (ref "R18") (pin "1") (pinfunction "1_1") (pintype "passive"))
      (node (ref "R50") (pin "1") (pinfunction "1_1") (pintype "passive"))
      (node (ref "TP31") (pin "P$1") (pinfunction "P$1_P$1") (pintype "bidirectional"))
    )
    (net (code "109") (name "S10") (class "Default")
      (node (ref "Q85") (pin "D") (pinfunction "D_D") (pintype "passive"))
      (node (ref "R51") (pin "1") (pinfunction "1_1") (pintype "passive"))
      (node (ref "TP24") (pin "P$1") (pinfunction "P$1_P$1") (pintype "bidirectional"))
    )
    (net (code "110") (name "S10_N") (class "Default")
      (node (ref "Q47") (pin "D") (pinfunction "D_D") (pintype "passive"))
      (node (ref "Q85") (pin "G") (pinfunction "G_G") (pintype "passive"))
      (node (ref "R19") (pin "1") (pinfunction "1_1") (pintype "passive"))
      (node (ref "R52") (pin "1") (pinfunction "1_1") (pintype "passive"))
      (node (ref "TP32") (pin "P$1") (pinfunction "P$1_P$1") (pintype "bidirectional"))
    )
    (net (code "111") (name "S11") (class "Default")
      (node (ref "Q86") (pin "D") (pinfunction "D_D") (pintype "passive"))
      (node (ref "R53") (pin "1") (pinfunction "1_1") (pintype "passive"))
      (node (ref "TP25") (pin "P$1") (pinfunction "P$1_P$1") (pintype "bidirectional"))
    )
    (net (code "112") (name "S11_N") (class "Default")
      (node (ref "Q50") (pin "D") (pinfunction "D_D") (pintype "passive"))
      (node (ref "Q86") (pin "G") (pinfunction "G_G") (pintype "passive"))
      (node (ref "R20") (pin "1") (pinfunction "1_1") (pintype "passive"))
      (node (ref "R54") (pin "1") (pinfunction "1_1") (pintype "passive"))
      (node (ref "TP33") (pin "P$1") (pinfunction "P$1_P$1") (pintype "bidirectional"))
    )
    (net (code "113") (name "S12") (class "Default")
      (node (ref "Q87") (pin "D") (pinfunction "D_D") (pintype "passive"))
      (node (ref "R55") (pin "1") (pinfunction "1_1") (pintype "passive"))
      (node (ref "TP26") (pin "P$1") (pinfunction "P$1_P$1") (pintype "bidirectional"))
    )
    (net (code "114") (name "S12_N") (class "Default")
      (node (ref "Q53") (pin "D") (pinfunction "D_D") (pintype "passive"))
      (node (ref "Q87") (pin "G") (pinfunction "G_G") (pintype "passive"))
      (node (ref "R21") (pin "1") (pinfunction "1_1") (pintype "passive"))
      (node (ref "R56") (pin "1") (pinfunction "1_1") (pintype "passive"))
      (node (ref "TP34") (pin "P$1") (pinfunction "P$1_P$1") (pintype "bidirectional"))
    )
    (net (code "115") (name "S13") (class "Default")
      (node (ref "Q88") (pin "D") (pinfunction "D_D") (pintype "passive"))
      (node (ref "R57") (pin "1") (pinfunction "1_1") (pintype "passive"))
      (node (ref "TP27") (pin "P$1") (pinfunction "P$1_P$1") (pintype "bidirectional"))
    )
    (net (code "116") (name "S13_N") (class "Default")
      (node (ref "Q56") (pin "D") (pinfunction "D_D") (pintype "passive"))
      (node (ref "Q88") (pin "G") (pinfunction "G_G") (pintype "passive"))
      (node (ref "R22") (pin "1") (pinfunction "1_1") (pintype "passive"))
      (node (ref "R58") (pin "1") (pinfunction "1_1") (pintype "passive"))
      (node (ref "TP35") (pin "P$1") (pinfunction "P$1_P$1") (pintype "bidirectional"))
    )
    (net (code "117") (name "S14") (class "Default")
      (node (ref "Q89") (pin "D") (pinfunction "D_D") (pintype "passive"))
      (node (ref "R59") (pin "1") (pinfunction "1_1") (pintype "passive"))
      (node (ref "TP28") (pin "P$1") (pinfunction "P$1_P$1") (pintype "bidirectional"))
    )
    (net (code "118") (name "S14_N") (class "Default")
      (node (ref "Q59") (pin "D") (pinfunction "D_D") (pintype "passive"))
      (node (ref "Q89") (pin "G") (pinfunction "G_G") (pintype "passive"))
      (node (ref "R23") (pin "1") (pinfunction "1_1") (pintype "passive"))
      (node (ref "R60") (pin "1") (pinfunction "1_1") (pintype "passive"))
      (node (ref "TP36") (pin "P$1") (pinfunction "P$1_P$1") (pintype "bidirectional"))
    )
    (net (code "119") (name "S15") (class "Default")
      (node (ref "Q90") (pin "D") (pinfunction "D_D") (pintype "passive"))
      (node (ref "R61") (pin "1") (pinfunction "1_1") (pintype "passive"))
      (node (ref "TP29") (pin "P$1") (pinfunction "P$1_P$1") (pintype "bidirectional"))
    )
    (net (code "120") (name "S15_N") (class "Default")
      (node (ref "Q62") (pin "D") (pinfunction "D_D") (pintype "passive"))
      (node (ref "Q90") (pin "G") (pinfunction "G_G") (pintype "passive"))
      (node (ref "R24") (pin "1") (pinfunction "1_1") (pintype "passive"))
      (node (ref "R62") (pin "1") (pinfunction "1_1") (pintype "passive"))
      (node (ref "TP37") (pin "P$1") (pinfunction "P$1_P$1") (pintype "bidirectional"))
    )
  )
)
